# protoboard_rev01.net
KiCad netlist of a schematic drawn in EAGLE
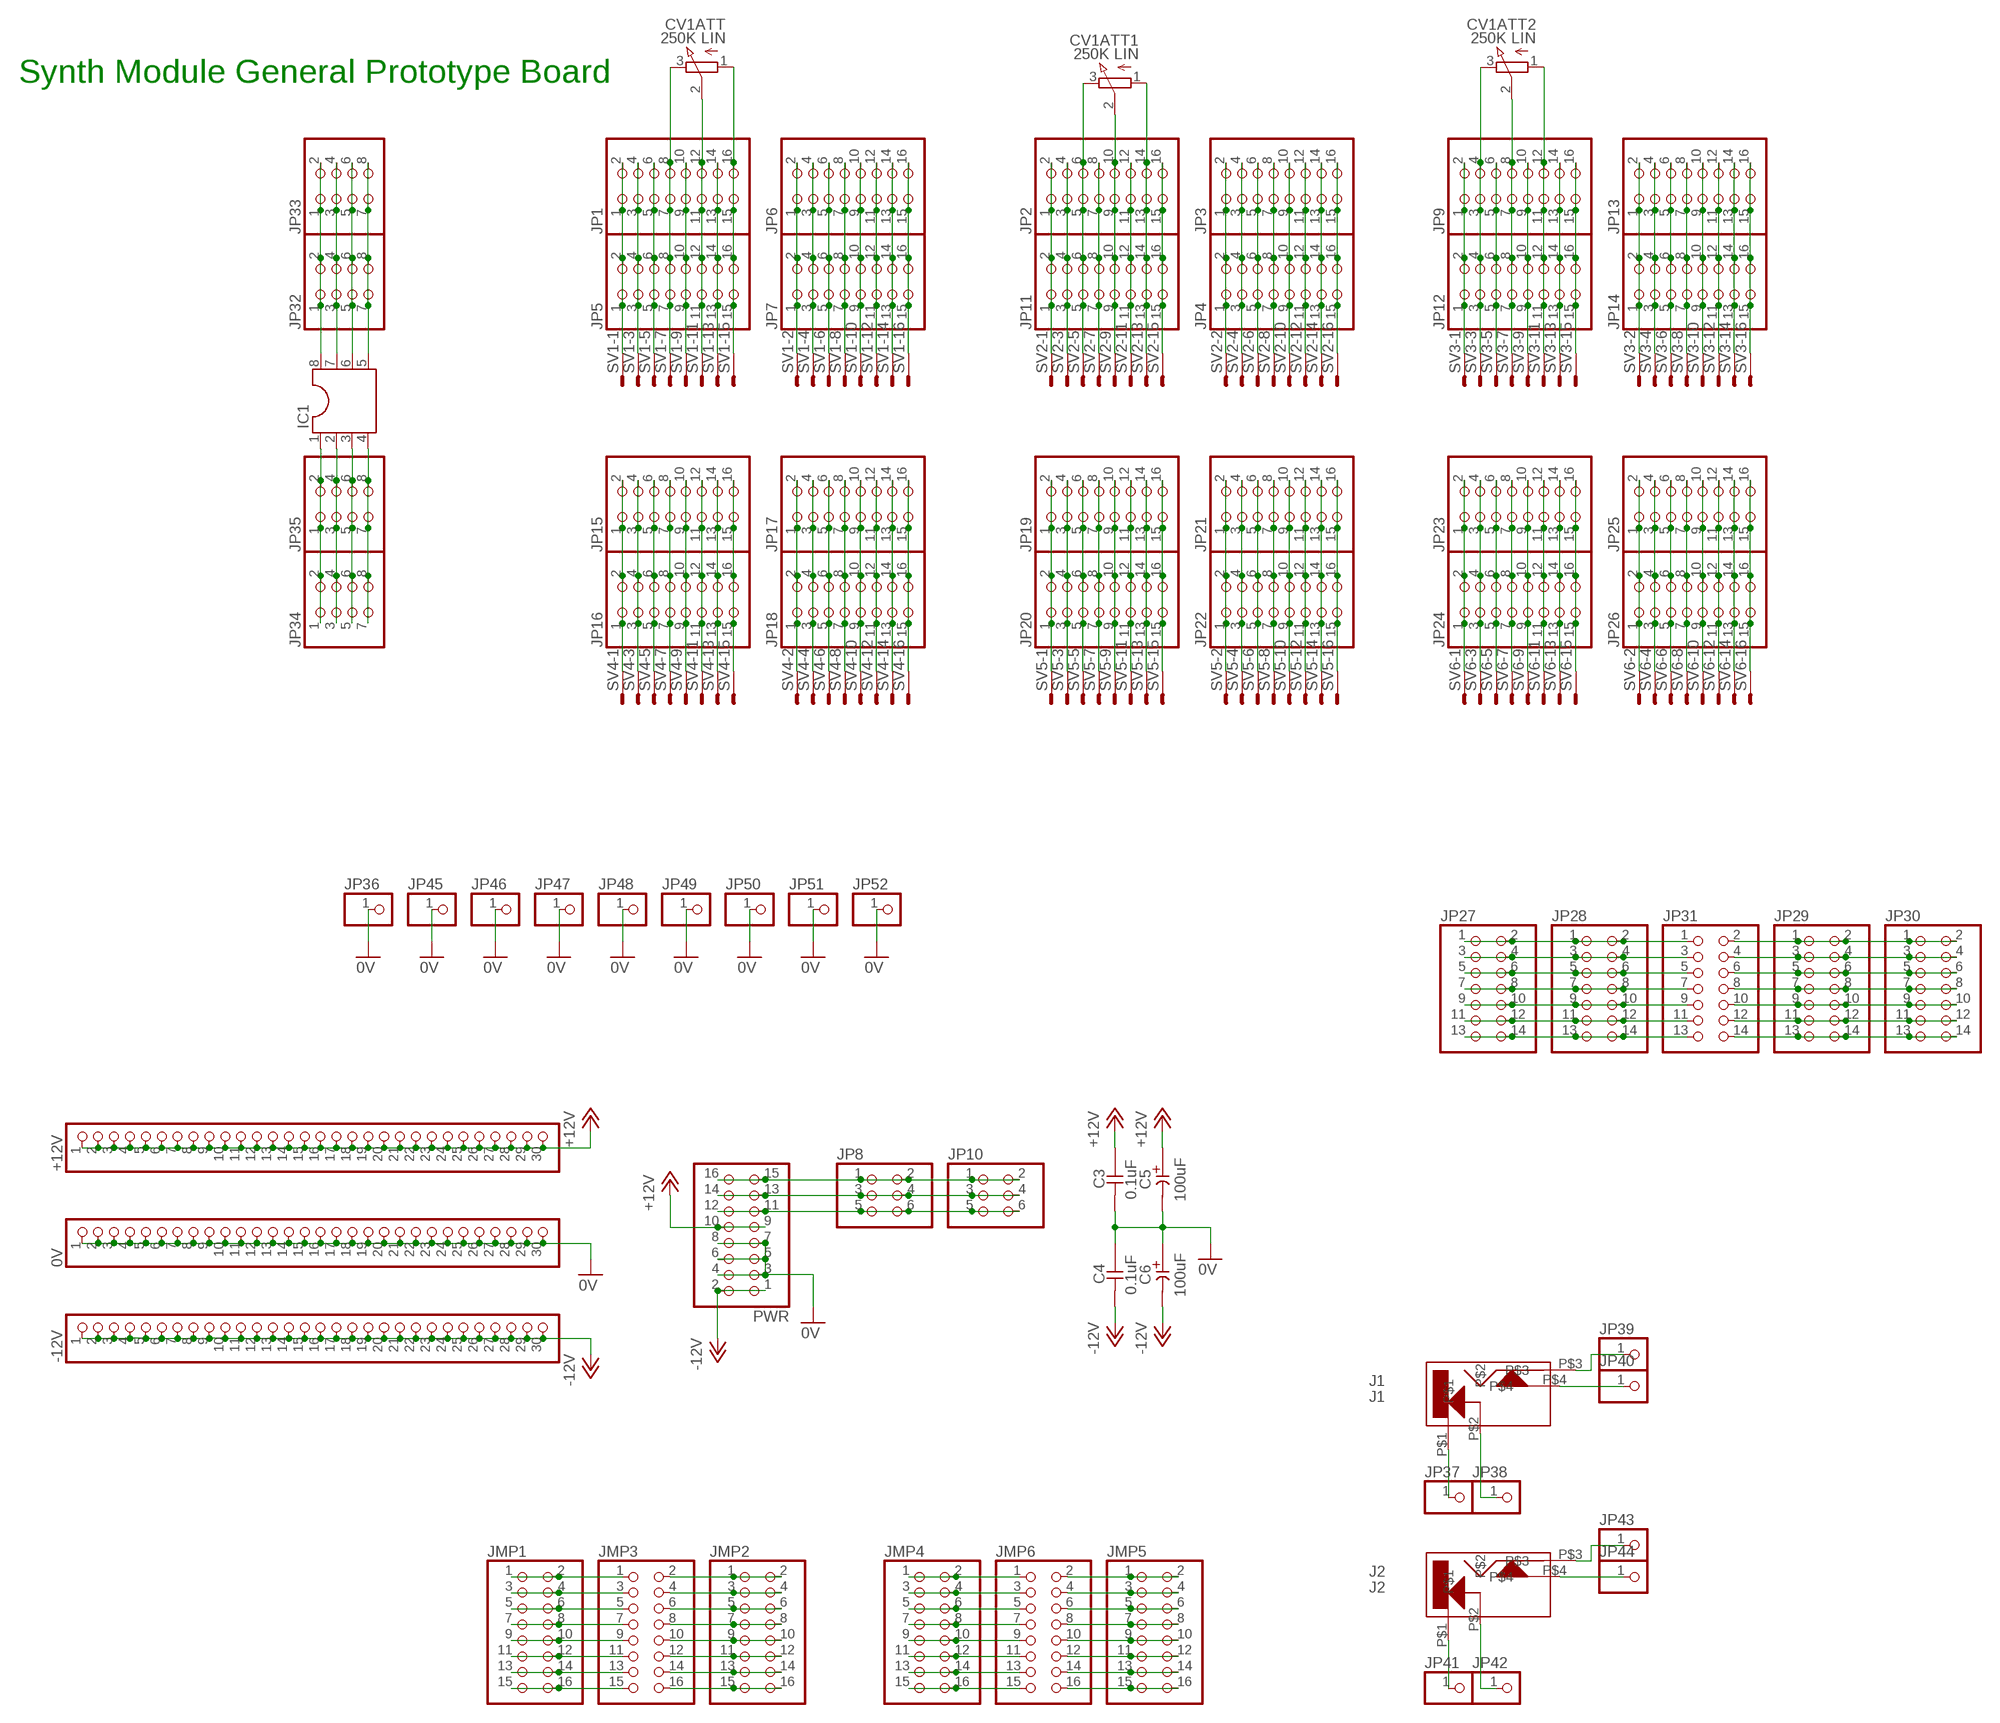
[diagram p0: schematic, sheet 1]

(export (version "E")
  (design (tool "Eeschema 10.0.6"))
  (components
    (comp (ref "+12V")
      (value "PINHD-1X30")
      (footprint "eagle-import:1X30")
      (libsource (lib "eagle-import") (part "PINHD-1X30"))
    )
    (comp (ref "-12V")
      (value "PINHD-1X30")
      (footprint "eagle-import:1X30")
      (libsource (lib "eagle-import") (part "PINHD-1X30"))
    )
    (comp (ref "0V")
      (value "PINHD-1X30")
      (footprint "eagle-import:1X30")
      (libsource (lib "eagle-import") (part "PINHD-1X30"))
    )
    (comp (ref "C3")
      (value "0.1uF")
      (footprint "eagle-import:C025-024X044")
      (libsource (lib "eagle-import") (part "CC-US025-024X044"))
    )
    (comp (ref "C4")
      (value "0.1uF")
      (footprint "eagle-import:C025-024X044")
      (libsource (lib "eagle-import") (part "CC-US025-024X044"))
    )
    (comp (ref "C5")
      (value "100uF")
      (footprint "eagle-import:E5-8,5")
      (libsource (lib "eagle-import") (part "CE-USE5-8.5"))
    )
    (comp (ref "C6")
      (value "100uF")
      (footprint "eagle-import:E5-8,5")
      (libsource (lib "eagle-import") (part "CE-USE5-8.5"))
    )
    (comp (ref "CV1ATT")
      (value "250K LIN")
      (footprint "eagle-import:3RP_1610N")
      (libsource (lib "eagle-import") (part "3RP/1610N"))
    )
    (comp (ref "CV1ATT1")
      (value "250K LIN")
      (footprint "eagle-import:3RP_1610N")
      (libsource (lib "eagle-import") (part "3RP/1610N"))
    )
    (comp (ref "CV1ATT2")
      (value "250K LIN")
      (footprint "eagle-import:3RP_1610N")
      (libsource (lib "eagle-import") (part "3RP/1610N"))
    )
    (comp (ref "IC1")
      (value "DIL8S")
      (footprint "eagle-import:SOCKET-08")
      (libsource (lib "eagle-import") (part "DIL8S"))
    )
    (comp (ref "J1")
      (value "J1")
      (footprint "eagle-import:CL1384")
      (libsource (lib "eagle-import") (part "CL1384"))
    )
    (comp (ref "J2")
      (value "J2")
      (footprint "eagle-import:CL1384")
      (libsource (lib "eagle-import") (part "CL1384"))
    )
    (comp (ref "JMP1")
      (value "PINHD-2X8")
      (footprint "eagle-import:2X08")
      (libsource (lib "eagle-import") (part "PINHD-2X8"))
    )
    (comp (ref "JMP2")
      (value "PINHD-2X8")
      (footprint "eagle-import:2X08")
      (libsource (lib "eagle-import") (part "PINHD-2X8"))
    )
    (comp (ref "JMP3")
      (value "PINHD-2X8")
      (footprint "eagle-import:2X08")
      (libsource (lib "eagle-import") (part "PINHD-2X8"))
    )
    (comp (ref "JMP4")
      (value "PINHD-2X8")
      (footprint "eagle-import:2X08")
      (libsource (lib "eagle-import") (part "PINHD-2X8"))
    )
    (comp (ref "JMP5")
      (value "PINHD-2X8")
      (footprint "eagle-import:2X08")
      (libsource (lib "eagle-import") (part "PINHD-2X8"))
    )
    (comp (ref "JMP6")
      (value "PINHD-2X8")
      (footprint "eagle-import:2X08")
      (libsource (lib "eagle-import") (part "PINHD-2X8"))
    )
    (comp (ref "JP1")
      (value "PINHD-2X8")
      (footprint "eagle-import:2X08")
      (libsource (lib "eagle-import") (part "PINHD-2X8"))
    )
    (comp (ref "JP2")
      (value "PINHD-2X8")
      (footprint "eagle-import:2X08")
      (libsource (lib "eagle-import") (part "PINHD-2X8"))
    )
    (comp (ref "JP3")
      (value "PINHD-2X8")
      (footprint "eagle-import:2X08")
      (libsource (lib "eagle-import") (part "PINHD-2X8"))
    )
    (comp (ref "JP4")
      (value "PINHD-2X8")
      (footprint "eagle-import:2X08")
      (libsource (lib "eagle-import") (part "PINHD-2X8"))
    )
    (comp (ref "JP5")
      (value "PINHD-2X8")
      (footprint "eagle-import:2X08")
      (libsource (lib "eagle-import") (part "PINHD-2X8"))
    )
    (comp (ref "JP6")
      (value "PINHD-2X8")
      (footprint "eagle-import:2X08")
      (libsource (lib "eagle-import") (part "PINHD-2X8"))
    )
    (comp (ref "JP7")
      (value "PINHD-2X8")
      (footprint "eagle-import:2X08")
      (libsource (lib "eagle-import") (part "PINHD-2X8"))
    )
    (comp (ref "JP8")
      (value "PINHD-2X3")
      (footprint "eagle-import:2X03")
      (libsource (lib "eagle-import") (part "PINHD-2X3"))
    )
    (comp (ref "JP9")
      (value "PINHD-2X8")
      (footprint "eagle-import:2X08")
      (libsource (lib "eagle-import") (part "PINHD-2X8"))
    )
    (comp (ref "JP10")
      (value "PINHD-2X3")
      (footprint "eagle-import:2X03")
      (libsource (lib "eagle-import") (part "PINHD-2X3"))
    )
    (comp (ref "JP11")
      (value "PINHD-2X8")
      (footprint "eagle-import:2X08")
      (libsource (lib "eagle-import") (part "PINHD-2X8"))
    )
    (comp (ref "JP12")
      (value "PINHD-2X8")
      (footprint "eagle-import:2X08")
      (libsource (lib "eagle-import") (part "PINHD-2X8"))
    )
    (comp (ref "JP13")
      (value "PINHD-2X8")
      (footprint "eagle-import:2X08")
      (libsource (lib "eagle-import") (part "PINHD-2X8"))
    )
    (comp (ref "JP14")
      (value "PINHD-2X8")
      (footprint "eagle-import:2X08")
      (libsource (lib "eagle-import") (part "PINHD-2X8"))
    )
    (comp (ref "JP15")
      (value "PINHD-2X8")
      (footprint "eagle-import:2X08")
      (libsource (lib "eagle-import") (part "PINHD-2X8"))
    )
    (comp (ref "JP16")
      (value "PINHD-2X8")
      (footprint "eagle-import:2X08")
      (libsource (lib "eagle-import") (part "PINHD-2X8"))
    )
    (comp (ref "JP17")
      (value "PINHD-2X8")
      (footprint "eagle-import:2X08")
      (libsource (lib "eagle-import") (part "PINHD-2X8"))
    )
    (comp (ref "JP18")
      (value "PINHD-2X8")
      (footprint "eagle-import:2X08")
      (libsource (lib "eagle-import") (part "PINHD-2X8"))
    )
    (comp (ref "JP19")
      (value "PINHD-2X8")
      (footprint "eagle-import:2X08")
      (libsource (lib "eagle-import") (part "PINHD-2X8"))
    )
    (comp (ref "JP20")
      (value "PINHD-2X8")
      (footprint "eagle-import:2X08")
      (libsource (lib "eagle-import") (part "PINHD-2X8"))
    )
    (comp (ref "JP21")
      (value "PINHD-2X8")
      (footprint "eagle-import:2X08")
      (libsource (lib "eagle-import") (part "PINHD-2X8"))
    )
    (comp (ref "JP22")
      (value "PINHD-2X8")
      (footprint "eagle-import:2X08")
      (libsource (lib "eagle-import") (part "PINHD-2X8"))
    )
    (comp (ref "JP23")
      (value "PINHD-2X8")
      (footprint "eagle-import:2X08")
      (libsource (lib "eagle-import") (part "PINHD-2X8"))
    )
    (comp (ref "JP24")
      (value "PINHD-2X8")
      (footprint "eagle-import:2X08")
      (libsource (lib "eagle-import") (part "PINHD-2X8"))
    )
    (comp (ref "JP25")
      (value "PINHD-2X8")
      (footprint "eagle-import:2X08")
      (libsource (lib "eagle-import") (part "PINHD-2X8"))
    )
    (comp (ref "JP26")
      (value "PINHD-2X8")
      (footprint "eagle-import:2X08")
      (libsource (lib "eagle-import") (part "PINHD-2X8"))
    )
    (comp (ref "JP27")
      (value "PINHD-2X7")
      (footprint "eagle-import:2X07")
      (libsource (lib "eagle-import") (part "PINHD-2X7"))
    )
    (comp (ref "JP28")
      (value "PINHD-2X7")
      (footprint "eagle-import:2X07")
      (libsource (lib "eagle-import") (part "PINHD-2X7"))
    )
    (comp (ref "JP29")
      (value "PINHD-2X7")
      (footprint "eagle-import:2X07")
      (libsource (lib "eagle-import") (part "PINHD-2X7"))
    )
    (comp (ref "JP30")
      (value "PINHD-2X7")
      (footprint "eagle-import:2X07")
      (libsource (lib "eagle-import") (part "PINHD-2X7"))
    )
    (comp (ref "JP31")
      (value "PINHD-2X7")
      (footprint "eagle-import:2X07")
      (libsource (lib "eagle-import") (part "PINHD-2X7"))
    )
    (comp (ref "JP32")
      (value "PINHD-2X4")
      (footprint "eagle-import:2X04")
      (libsource (lib "eagle-import") (part "PINHD-2X4"))
    )
    (comp (ref "JP33")
      (value "PINHD-2X4")
      (footprint "eagle-import:2X04")
      (libsource (lib "eagle-import") (part "PINHD-2X4"))
    )
    (comp (ref "JP34")
      (value "PINHD-2X4")
      (footprint "eagle-import:2X04")
      (libsource (lib "eagle-import") (part "PINHD-2X4"))
    )
    (comp (ref "JP35")
      (value "PINHD-2X4")
      (footprint "eagle-import:2X04")
      (libsource (lib "eagle-import") (part "PINHD-2X4"))
    )
    (comp (ref "JP36")
      (value "PINHD-1X1")
      (footprint "eagle-import:1X01")
      (libsource (lib "eagle-import") (part "PINHD-1X1"))
    )
    (comp (ref "JP37")
      (value "PINHD-1X1")
      (footprint "eagle-import:1X01")
      (libsource (lib "eagle-import") (part "PINHD-1X1"))
    )
    (comp (ref "JP38")
      (value "PINHD-1X1")
      (footprint "eagle-import:1X01")
      (libsource (lib "eagle-import") (part "PINHD-1X1"))
    )
    (comp (ref "JP39")
      (value "PINHD-1X1")
      (footprint "eagle-import:1X01")
      (libsource (lib "eagle-import") (part "PINHD-1X1"))
    )
    (comp (ref "JP40")
      (value "PINHD-1X1")
      (footprint "eagle-import:1X01")
      (libsource (lib "eagle-import") (part "PINHD-1X1"))
    )
    (comp (ref "JP41")
      (value "PINHD-1X1")
      (footprint "eagle-import:1X01")
      (libsource (lib "eagle-import") (part "PINHD-1X1"))
    )
    (comp (ref "JP42")
      (value "PINHD-1X1")
      (footprint "eagle-import:1X01")
      (libsource (lib "eagle-import") (part "PINHD-1X1"))
    )
    (comp (ref "JP43")
      (value "PINHD-1X1")
      (footprint "eagle-import:1X01")
      (libsource (lib "eagle-import") (part "PINHD-1X1"))
    )
    (comp (ref "JP44")
      (value "PINHD-1X1")
      (footprint "eagle-import:1X01")
      (libsource (lib "eagle-import") (part "PINHD-1X1"))
    )
    (comp (ref "JP45")
      (value "PINHD-1X1")
      (footprint "eagle-import:1X01")
      (libsource (lib "eagle-import") (part "PINHD-1X1"))
    )
    (comp (ref "JP46")
      (value "PINHD-1X1")
      (footprint "eagle-import:1X01")
      (libsource (lib "eagle-import") (part "PINHD-1X1"))
    )
    (comp (ref "JP47")
      (value "PINHD-1X1")
      (footprint "eagle-import:1X01")
      (libsource (lib "eagle-import") (part "PINHD-1X1"))
    )
    (comp (ref "JP48")
      (value "PINHD-1X1")
      (footprint "eagle-import:1X01")
      (libsource (lib "eagle-import") (part "PINHD-1X1"))
    )
    (comp (ref "JP49")
      (value "PINHD-1X1")
      (footprint "eagle-import:1X01")
      (libsource (lib "eagle-import") (part "PINHD-1X1"))
    )
    (comp (ref "JP50")
      (value "PINHD-1X1")
      (footprint "eagle-import:1X01")
      (libsource (lib "eagle-import") (part "PINHD-1X1"))
    )
    (comp (ref "JP51")
      (value "PINHD-1X1")
      (footprint "eagle-import:1X01")
      (libsource (lib "eagle-import") (part "PINHD-1X1"))
    )
    (comp (ref "JP52")
      (value "PINHD-1X1")
      (footprint "eagle-import:1X01")
      (libsource (lib "eagle-import") (part "PINHD-1X1"))
    )
    (comp (ref "PWR")
      (value "PINHD-2X8")
      (footprint "eagle-import:2X08")
      (libsource (lib "eagle-import") (part "PINHD-2X8"))
    )
    (comp (ref "SV1")
      (value "16E")
      (footprint "eagle-import:16P")
      (libsource (lib "eagle-import") (part "16E"))
    )
    (comp (ref "SV2")
      (value "16E")
      (footprint "eagle-import:16P")
      (libsource (lib "eagle-import") (part "16E"))
    )
    (comp (ref "SV3")
      (value "16E")
      (footprint "eagle-import:16P")
      (libsource (lib "eagle-import") (part "16E"))
    )
    (comp (ref "SV4")
      (value "16E")
      (footprint "eagle-import:16P")
      (libsource (lib "eagle-import") (part "16E"))
    )
    (comp (ref "SV5")
      (value "16E")
      (footprint "eagle-import:16P")
      (libsource (lib "eagle-import") (part "16E"))
    )
    (comp (ref "SV6")
      (value "16E")
      (footprint "eagle-import:16P")
      (libsource (lib "eagle-import") (part "16E"))
    )
  )
  (nets
    (net (code "1") (name "+12V") (class "Default")
      (node (ref "+12V") (pin "1") (pinfunction "1_1") (pintype "passive"))
      (node (ref "+12V") (pin "10") (pinfunction "10_10") (pintype "passive"))
      (node (ref "+12V") (pin "11") (pinfunction "11_11") (pintype "passive"))
      (node (ref "+12V") (pin "12") (pinfunction "12_12") (pintype "passive"))
      (node (ref "+12V") (pin "13") (pinfunction "13_13") (pintype "passive"))
      (node (ref "+12V") (pin "14") (pinfunction "14_14") (pintype "passive"))
      (node (ref "+12V") (pin "15") (pinfunction "15_15") (pintype "passive"))
      (node (ref "+12V") (pin "16") (pinfunction "16_16") (pintype "passive"))
      (node (ref "+12V") (pin "17") (pinfunction "17_17") (pintype "passive"))
      (node (ref "+12V") (pin "18") (pinfunction "18_18") (pintype "passive"))
      (node (ref "+12V") (pin "19") (pinfunction "19_19") (pintype "passive"))
      (node (ref "+12V") (pin "2") (pinfunction "2_2") (pintype "passive"))
      (node (ref "+12V") (pin "20") (pinfunction "20_20") (pintype "passive"))
      (node (ref "+12V") (pin "21") (pinfunction "21_21") (pintype "passive"))
      (node (ref "+12V") (pin "22") (pinfunction "22_22") (pintype "passive"))
      (node (ref "+12V") (pin "23") (pinfunction "23_23") (pintype "passive"))
      (node (ref "+12V") (pin "24") (pinfunction "24_24") (pintype "passive"))
      (node (ref "+12V") (pin "25") (pinfunction "25_25") (pintype "passive"))
      (node (ref "+12V") (pin "26") (pinfunction "26_26") (pintype "passive"))
      (node (ref "+12V") (pin "27") (pinfunction "27_27") (pintype "passive"))
      (node (ref "+12V") (pin "28") (pinfunction "28_28") (pintype "passive"))
      (node (ref "+12V") (pin "29") (pinfunction "29_29") (pintype "passive"))
      (node (ref "+12V") (pin "3") (pinfunction "3_3") (pintype "passive"))
      (node (ref "+12V") (pin "30") (pinfunction "30_30") (pintype "passive"))
      (node (ref "+12V") (pin "4") (pinfunction "4_4") (pintype "passive"))
      (node (ref "+12V") (pin "5") (pinfunction "5_5") (pintype "passive"))
      (node (ref "+12V") (pin "6") (pinfunction "6_6") (pintype "passive"))
      (node (ref "+12V") (pin "7") (pinfunction "7_7") (pintype "passive"))
      (node (ref "+12V") (pin "8") (pinfunction "8_8") (pintype "passive"))
      (node (ref "+12V") (pin "9") (pinfunction "9_9") (pintype "passive"))
      (node (ref "C3") (pin "1") (pinfunction "1_1") (pintype "passive"))
      (node (ref "C5") (pin "+") (pinfunction "+_+") (pintype "passive"))
      (node (ref "PWR") (pin "10") (pinfunction "10_10") (pintype "passive"))
      (node (ref "PWR") (pin "9") (pinfunction "9_9") (pintype "passive"))
    )
    (net (code "2") (name "-12V") (class "Default")
      (node (ref "-12V") (pin "1") (pinfunction "1_1") (pintype "passive"))
      (node (ref "-12V") (pin "10") (pinfunction "10_10") (pintype "passive"))
      (node (ref "-12V") (pin "11") (pinfunction "11_11") (pintype "passive"))
      (node (ref "-12V") (pin "12") (pinfunction "12_12") (pintype "passive"))
      (node (ref "-12V") (pin "13") (pinfunction "13_13") (pintype "passive"))
      (node (ref "-12V") (pin "14") (pinfunction "14_14") (pintype "passive"))
      (node (ref "-12V") (pin "15") (pinfunction "15_15") (pintype "passive"))
      (node (ref "-12V") (pin "16") (pinfunction "16_16") (pintype "passive"))
      (node (ref "-12V") (pin "17") (pinfunction "17_17") (pintype "passive"))
      (node (ref "-12V") (pin "18") (pinfunction "18_18") (pintype "passive"))
      (node (ref "-12V") (pin "19") (pinfunction "19_19") (pintype "passive"))
      (node (ref "-12V") (pin "2") (pinfunction "2_2") (pintype "passive"))
      (node (ref "-12V") (pin "20") (pinfunction "20_20") (pintype "passive"))
      (node (ref "-12V") (pin "21") (pinfunction "21_21") (pintype "passive"))
      (node (ref "-12V") (pin "22") (pinfunction "22_22") (pintype "passive"))
      (node (ref "-12V") (pin "23") (pinfunction "23_23") (pintype "passive"))
      (node (ref "-12V") (pin "24") (pinfunction "24_24") (pintype "passive"))
      (node (ref "-12V") (pin "25") (pinfunction "25_25") (pintype "passive"))
      (node (ref "-12V") (pin "26") (pinfunction "26_26") (pintype "passive"))
      (node (ref "-12V") (pin "27") (pinfunction "27_27") (pintype "passive"))
      (node (ref "-12V") (pin "28") (pinfunction "28_28") (pintype "passive"))
      (node (ref "-12V") (pin "29") (pinfunction "29_29") (pintype "passive"))
      (node (ref "-12V") (pin "3") (pinfunction "3_3") (pintype "passive"))
      (node (ref "-12V") (pin "30") (pinfunction "30_30") (pintype "passive"))
      (node (ref "-12V") (pin "4") (pinfunction "4_4") (pintype "passive"))
      (node (ref "-12V") (pin "5") (pinfunction "5_5") (pintype "passive"))
      (node (ref "-12V") (pin "6") (pinfunction "6_6") (pintype "passive"))
      (node (ref "-12V") (pin "7") (pinfunction "7_7") (pintype "passive"))
      (node (ref "-12V") (pin "8") (pinfunction "8_8") (pintype "passive"))
      (node (ref "-12V") (pin "9") (pinfunction "9_9") (pintype "passive"))
      (node (ref "C4") (pin "2") (pinfunction "2_2") (pintype "passive"))
      (node (ref "C6") (pin "-") (pinfunction "-_-") (pintype "passive"))
      (node (ref "PWR") (pin "1") (pinfunction "1_1") (pintype "passive"))
      (node (ref "PWR") (pin "2") (pinfunction "2_2") (pintype "passive"))
    )
    (net (code "3") (name "0V") (class "Default")
      (node (ref "0V") (pin "1") (pinfunction "1_1") (pintype "passive"))
      (node (ref "0V") (pin "10") (pinfunction "10_10") (pintype "passive"))
      (node (ref "0V") (pin "11") (pinfunction "11_11") (pintype "passive"))
      (node (ref "0V") (pin "12") (pinfunction "12_12") (pintype "passive"))
      (node (ref "0V") (pin "13") (pinfunction "13_13") (pintype "passive"))
      (node (ref "0V") (pin "14") (pinfunction "14_14") (pintype "passive"))
      (node (ref "0V") (pin "15") (pinfunction "15_15") (pintype "passive"))
      (node (ref "0V") (pin "16") (pinfunction "16_16") (pintype "passive"))
      (node (ref "0V") (pin "17") (pinfunction "17_17") (pintype "passive"))
      (node (ref "0V") (pin "18") (pinfunction "18_18") (pintype "passive"))
      (node (ref "0V") (pin "19") (pinfunction "19_19") (pintype "passive"))
      (node (ref "0V") (pin "2") (pinfunction "2_2") (pintype "passive"))
      (node (ref "0V") (pin "20") (pinfunction "20_20") (pintype "passive"))
      (node (ref "0V") (pin "21") (pinfunction "21_21") (pintype "passive"))
      (node (ref "0V") (pin "22") (pinfunction "22_22") (pintype "passive"))
      (node (ref "0V") (pin "23") (pinfunction "23_23") (pintype "passive"))
      (node (ref "0V") (pin "24") (pinfunction "24_24") (pintype "passive"))
      (node (ref "0V") (pin "25") (pinfunction "25_25") (pintype "passive"))
      (node (ref "0V") (pin "26") (pinfunction "26_26") (pintype "passive"))
      (node (ref "0V") (pin "27") (pinfunction "27_27") (pintype "passive"))
      (node (ref "0V") (pin "28") (pinfunction "28_28") (pintype "passive"))
      (node (ref "0V") (pin "29") (pinfunction "29_29") (pintype "passive"))
      (node (ref "0V") (pin "3") (pinfunction "3_3") (pintype "passive"))
      (node (ref "0V") (pin "30") (pinfunction "30_30") (pintype "passive"))
      (node (ref "0V") (pin "4") (pinfunction "4_4") (pintype "passive"))
      (node (ref "0V") (pin "5") (pinfunction "5_5") (pintype "passive"))
      (node (ref "0V") (pin "6") (pinfunction "6_6") (pintype "passive"))
      (node (ref "0V") (pin "7") (pinfunction "7_7") (pintype "passive"))
      (node (ref "0V") (pin "8") (pinfunction "8_8") (pintype "passive"))
      (node (ref "0V") (pin "9") (pinfunction "9_9") (pintype "passive"))
      (node (ref "C3") (pin "2") (pinfunction "2_2") (pintype "passive"))
      (node (ref "C4") (pin "1") (pinfunction "1_1") (pintype "passive"))
      (node (ref "C5") (pin "-") (pinfunction "-_-") (pintype "passive"))
      (node (ref "C6") (pin "+") (pinfunction "+_+") (pintype "passive"))
      (node (ref "JP36") (pin "1") (pinfunction "1_1") (pintype "passive"))
      (node (ref "JP45") (pin "1") (pinfunction "1_1") (pintype "passive"))
      (node (ref "JP46") (pin "1") (pinfunction "1_1") (pintype "passive"))
      (node (ref "JP47") (pin "1") (pinfunction "1_1") (pintype "passive"))
      (node (ref "JP48") (pin "1") (pinfunction "1_1") (pintype "passive"))
      (node (ref "JP49") (pin "1") (pinfunction "1_1") (pintype "passive"))
      (node (ref "JP50") (pin "1") (pinfunction "1_1") (pintype "passive"))
      (node (ref "JP51") (pin "1") (pinfunction "1_1") (pintype "passive"))
      (node (ref "JP52") (pin "1") (pinfunction "1_1") (pintype "passive"))
      (node (ref "PWR") (pin "3") (pinfunction "3_3") (pintype "passive"))
      (node (ref "PWR") (pin "4") (pinfunction "4_4") (pintype "passive"))
      (node (ref "PWR") (pin "5") (pinfunction "5_5") (pintype "passive"))
      (node (ref "PWR") (pin "6") (pinfunction "6_6") (pintype "passive"))
      (node (ref "PWR") (pin "7") (pinfunction "7_7") (pintype "passive"))
      (node (ref "PWR") (pin "8") (pinfunction "8_8") (pintype "passive"))
    )
    (net (code "4") (name "Net-(CV1ATT-A)") (class "Default")
      (node (ref "CV1ATT") (pin "1") (pinfunction "A_1") (pintype "passive"))
      (node (ref "JP1") (pin "15") (pinfunction "15_15") (pintype "passive"))
      (node (ref "JP1") (pin "16") (pinfunction "16_16") (pintype "passive"))
      (node (ref "JP5") (pin "15") (pinfunction "15_15") (pintype "passive"))
      (node (ref "JP5") (pin "16") (pinfunction "16_16") (pintype "passive"))
      (node (ref "SV1") (pin "15") (pinfunction "S_15") (pintype "passive"))
    )
    (net (code "5") (name "Net-(CV1ATT-E)") (class "Default")
      (node (ref "CV1ATT") (pin "3") (pinfunction "E_3") (pintype "passive"))
      (node (ref "JP1") (pin "7") (pinfunction "7_7") (pintype "passive"))
      (node (ref "JP1") (pin "8") (pinfunction "8_8") (pintype "passive"))
      (node (ref "JP5") (pin "7") (pinfunction "7_7") (pintype "passive"))
      (node (ref "JP5") (pin "8") (pinfunction "8_8") (pintype "passive"))
      (node (ref "SV1") (pin "7") (pinfunction "S_7") (pintype "passive"))
    )
    (net (code "6") (name "Net-(CV1ATT-S)") (class "Default")
      (node (ref "CV1ATT") (pin "2") (pinfunction "S_2") (pintype "passive"))
      (node (ref "JP1") (pin "11") (pinfunction "11_11") (pintype "passive"))
      (node (ref "JP1") (pin "12") (pinfunction "12_12") (pintype "passive"))
      (node (ref "JP5") (pin "11") (pinfunction "11_11") (pintype "passive"))
      (node (ref "JP5") (pin "12") (pinfunction "12_12") (pintype "passive"))
      (node (ref "SV1") (pin "11") (pinfunction "S_11") (pintype "passive"))
    )
    (net (code "7") (name "Net-(CV1ATT1-A)") (class "Default")
      (node (ref "CV1ATT1") (pin "1") (pinfunction "A_1") (pintype "passive"))
      (node (ref "JP11") (pin "13") (pinfunction "13_13") (pintype "passive"))
      (node (ref "JP11") (pin "14") (pinfunction "14_14") (pintype "passive"))
      (node (ref "JP2") (pin "13") (pinfunction "13_13") (pintype "passive"))
      (node (ref "JP2") (pin "14") (pinfunction "14_14") (pintype "passive"))
      (node (ref "SV2") (pin "13") (pinfunction "S_13") (pintype "passive"))
    )
    (net (code "8") (name "Net-(CV1ATT1-E)") (class "Default")
      (node (ref "CV1ATT1") (pin "3") (pinfunction "E_3") (pintype "passive"))
      (node (ref "JP11") (pin "5") (pinfunction "5_5") (pintype "passive"))
      (node (ref "JP11") (pin "6") (pinfunction "6_6") (pintype "passive"))
      (node (ref "JP2") (pin "5") (pinfunction "5_5") (pintype "passive"))
      (node (ref "JP2") (pin "6") (pinfunction "6_6") (pintype "passive"))
      (node (ref "SV2") (pin "5") (pinfunction "S_5") (pintype "passive"))
    )
    (net (code "9") (name "Net-(CV1ATT1-S)") (class "Default")
      (node (ref "CV1ATT1") (pin "2") (pinfunction "S_2") (pintype "passive"))
      (node (ref "JP11") (pin "10") (pinfunction "10_10") (pintype "passive"))
      (node (ref "JP11") (pin "9") (pinfunction "9_9") (pintype "passive"))
      (node (ref "JP2") (pin "10") (pinfunction "10_10") (pintype "passive"))
      (node (ref "JP2") (pin "9") (pinfunction "9_9") (pintype "passive"))
      (node (ref "SV2") (pin "9") (pinfunction "S_9") (pintype "passive"))
    )
    (net (code "10") (name "Net-(CV1ATT2-A)") (class "Default")
      (node (ref "CV1ATT2") (pin "1") (pinfunction "A_1") (pintype "passive"))
      (node (ref "JP12") (pin "11") (pinfunction "11_11") (pintype "passive"))
      (node (ref "JP12") (pin "12") (pinfunction "12_12") (pintype "passive"))
      (node (ref "JP9") (pin "11") (pinfunction "11_11") (pintype "passive"))
      (node (ref "JP9") (pin "12") (pinfunction "12_12") (pintype "passive"))
      (node (ref "SV3") (pin "11") (pinfunction "S_11") (pintype "passive"))
    )
    (net (code "11") (name "Net-(CV1ATT2-E)") (class "Default")
      (node (ref "CV1ATT2") (pin "3") (pinfunction "E_3") (pintype "passive"))
      (node (ref "JP12") (pin "3") (pinfunction "3_3") (pintype "passive"))
      (node (ref "JP12") (pin "4") (pinfunction "4_4") (pintype "passive"))
      (node (ref "JP9") (pin "3") (pinfunction "3_3") (pintype "passive"))
      (node (ref "JP9") (pin "4") (pinfunction "4_4") (pintype "passive"))
      (node (ref "SV3") (pin "3") (pinfunction "S_3") (pintype "passive"))
    )
    (net (code "12") (name "Net-(CV1ATT2-S)") (class "Default")
      (node (ref "CV1ATT2") (pin "2") (pinfunction "S_2") (pintype "passive"))
      (node (ref "JP12") (pin "7") (pinfunction "7_7") (pintype "passive"))
      (node (ref "JP12") (pin "8") (pinfunction "8_8") (pintype "passive"))
      (node (ref "JP9") (pin "7") (pinfunction "7_7") (pintype "passive"))
      (node (ref "JP9") (pin "8") (pinfunction "8_8") (pintype "passive"))
      (node (ref "SV3") (pin "7") (pinfunction "S_7") (pintype "passive"))
    )
    (net (code "13") (name "Net-(IC1-Pad1)") (class "Default")
      (node (ref "IC1") (pin "1") (pinfunction "1_1") (pintype "passive"))
      (node (ref "JP34") (pin "1") (pinfunction "1_1") (pintype "passive"))
      (node (ref "JP34") (pin "2") (pinfunction "2_2") (pintype "passive"))
      (node (ref "JP35") (pin "1") (pinfunction "1_1") (pintype "passive"))
      (node (ref "JP35") (pin "2") (pinfunction "2_2") (pintype "passive"))
    )
    (net (code "14") (name "Net-(IC1-Pad2)") (class "Default")
      (node (ref "IC1") (pin "2") (pinfunction "2_2") (pintype "passive"))
      (node (ref "JP34") (pin "3") (pinfunction "3_3") (pintype "passive"))
      (node (ref "JP34") (pin "4") (pinfunction "4_4") (pintype "passive"))
      (node (ref "JP35") (pin "3") (pinfunction "3_3") (pintype "passive"))
      (node (ref "JP35") (pin "4") (pinfunction "4_4") (pintype "passive"))
    )
    (net (code "15") (name "Net-(IC1-Pad3)") (class "Default")
      (node (ref "IC1") (pin "3") (pinfunction "3_3") (pintype "passive"))
      (node (ref "JP34") (pin "5") (pinfunction "5_5") (pintype "passive"))
      (node (ref "JP34") (pin "6") (pinfunction "6_6") (pintype "passive"))
      (node (ref "JP35") (pin "5") (pinfunction "5_5") (pintype "passive"))
      (node (ref "JP35") (pin "6") (pinfunction "6_6") (pintype "passive"))
    )
    (net (code "16") (name "Net-(IC1-Pad4)") (class "Default")
      (node (ref "IC1") (pin "4") (pinfunction "4_4") (pintype "passive"))
      (node (ref "JP34") (pin "7") (pinfunction "7_7") (pintype "passive"))
      (node (ref "JP34") (pin "8") (pinfunction "8_8") (pintype "passive"))
      (node (ref "JP35") (pin "7") (pinfunction "7_7") (pintype "passive"))
      (node (ref "JP35") (pin "8") (pinfunction "8_8") (pintype "passive"))
    )
    (net (code "17") (name "Net-(IC1-Pad5)") (class "Default")
      (node (ref "IC1") (pin "5") (pinfunction "5_5") (pintype "passive"))
      (node (ref "JP32") (pin "7") (pinfunction "7_7") (pintype "passive"))
      (node (ref "JP32") (pin "8") (pinfunction "8_8") (pintype "passive"))
      (node (ref "JP33") (pin "7") (pinfunction "7_7") (pintype "passive"))
      (node (ref "JP33") (pin "8") (pinfunction "8_8") (pintype "passive"))
    )
    (net (code "18") (name "Net-(IC1-Pad6)") (class "Default")
      (node (ref "IC1") (pin "6") (pinfunction "6_6") (pintype "passive"))
      (node (ref "JP32") (pin "5") (pinfunction "5_5") (pintype "passive"))
      (node (ref "JP32") (pin "6") (pinfunction "6_6") (pintype "passive"))
      (node (ref "JP33") (pin "5") (pinfunction "5_5") (pintype "passive"))
      (node (ref "JP33") (pin "6") (pinfunction "6_6") (pintype "passive"))
    )
    (net (code "19") (name "Net-(IC1-Pad7)") (class "Default")
      (node (ref "IC1") (pin "7") (pinfunction "7_7") (pintype "passive"))
      (node (ref "JP32") (pin "3") (pinfunction "3_3") (pintype "passive"))
      (node (ref "JP32") (pin "4") (pinfunction "4_4") (pintype "passive"))
      (node (ref "JP33") (pin "3") (pinfunction "3_3") (pintype "passive"))
      (node (ref "JP33") (pin "4") (pinfunction "4_4") (pintype "passive"))
    )
    (net (code "20") (name "Net-(IC1-Pad8)") (class "Default")
      (node (ref "IC1") (pin "8") (pinfunction "8_8") (pintype "passive"))
      (node (ref "JP32") (pin "1") (pinfunction "1_1") (pintype "passive"))
      (node (ref "JP32") (pin "2") (pinfunction "2_2") (pintype "passive"))
      (node (ref "JP33") (pin "1") (pinfunction "1_1") (pintype "passive"))
      (node (ref "JP33") (pin "2") (pinfunction "2_2") (pintype "passive"))
    )
    (net (code "21") (name "Net-(J1-PadP$1)") (class "Default")
      (node (ref "J1") (pin "P$1") (pinfunction "P$1_P$1") (pintype "bidirectional"))
      (node (ref "JP37") (pin "1") (pinfunction "1_1") (pintype "passive"))
    )
    (net (code "22") (name "Net-(J1-PadP$2)") (class "Default")
      (node (ref "J1") (pin "P$2") (pinfunction "P$2_P$2") (pintype "bidirectional"))
      (node (ref "JP38") (pin "1") (pinfunction "1_1") (pintype "passive"))
    )
    (net (code "23") (name "Net-(J1-PadP$3)") (class "Default")
      (node (ref "J1") (pin "P$3") (pinfunction "P$3_P$3") (pintype "bidirectional"))
      (node (ref "JP39") (pin "1") (pinfunction "1_1") (pintype "passive"))
    )
    (net (code "24") (name "Net-(J1-PadP$4)") (class "Default")
      (node (ref "J1") (pin "P$4") (pinfunction "P$4_P$4") (pintype "bidirectional"))
      (node (ref "JP40") (pin "1") (pinfunction "1_1") (pintype "passive"))
    )
    (net (code "25") (name "Net-(J2-PadP$1)") (class "Default")
      (node (ref "J2") (pin "P$1") (pinfunction "P$1_P$1") (pintype "bidirectional"))
      (node (ref "JP41") (pin "1") (pinfunction "1_1") (pintype "passive"))
    )
    (net (code "26") (name "Net-(J2-PadP$2)") (class "Default")
      (node (ref "J2") (pin "P$2") (pinfunction "P$2_P$2") (pintype "bidirectional"))
      (node (ref "JP42") (pin "1") (pinfunction "1_1") (pintype "passive"))
    )
    (net (code "27") (name "Net-(J2-PadP$3)") (class "Default")
      (node (ref "J2") (pin "P$3") (pinfunction "P$3_P$3") (pintype "bidirectional"))
      (node (ref "JP43") (pin "1") (pinfunction "1_1") (pintype "passive"))
    )
    (net (code "28") (name "Net-(J2-PadP$4)") (class "Default")
      (node (ref "J2") (pin "P$4") (pinfunction "P$4_P$4") (pintype "bidirectional"))
      (node (ref "JP44") (pin "1") (pinfunction "1_1") (pintype "passive"))
    )
    (net (code "29") (name "Net-(JMP1-Pad1)") (class "Default")
      (node (ref "JMP1") (pin "1") (pinfunction "1_1") (pintype "passive"))
      (node (ref "JMP1") (pin "2") (pinfunction "2_2") (pintype "passive"))
      (node (ref "JMP3") (pin "1") (pinfunction "1_1") (pintype "passive"))
    )
    (net (code "30") (name "Net-(JMP1-Pad3)") (class "Default")
      (node (ref "JMP1") (pin "3") (pinfunction "3_3") (pintype "passive"))
      (node (ref "JMP1") (pin "4") (pinfunction "4_4") (pintype "passive"))
      (node (ref "JMP3") (pin "3") (pinfunction "3_3") (pintype "passive"))
    )
    (net (code "31") (name "Net-(JMP1-Pad5)") (class "Default")
      (node (ref "JMP1") (pin "5") (pinfunction "5_5") (pintype "passive"))
      (node (ref "JMP1") (pin "6") (pinfunction "6_6") (pintype "passive"))
      (node (ref "JMP3") (pin "5") (pinfunction "5_5") (pintype "passive"))
    )
    (net (code "32") (name "Net-(JMP1-Pad7)") (class "Default")
      (node (ref "JMP1") (pin "7") (pinfunction "7_7") (pintype "passive"))
      (node (ref "JMP1") (pin "8") (pinfunction "8_8") (pintype "passive"))
      (node (ref "JMP3") (pin "7") (pinfunction "7_7") (pintype "passive"))
    )
    (net (code "33") (name "Net-(JMP1-Pad10)") (class "Default")
      (node (ref "JMP1") (pin "10") (pinfunction "10_10") (pintype "passive"))
      (node (ref "JMP1") (pin "9") (pinfunction "9_9") (pintype "passive"))
      (node (ref "JMP3") (pin "9") (pinfunction "9_9") (pintype "passive"))
    )
    (net (code "34") (name "Net-(JMP1-Pad11)") (class "Default")
      (node (ref "JMP1") (pin "11") (pinfunction "11_11") (pintype "passive"))
      (node (ref "JMP1") (pin "12") (pinfunction "12_12") (pintype "passive"))
      (node (ref "JMP3") (pin "11") (pinfunction "11_11") (pintype "passive"))
    )
    (net (code "35") (name "Net-(JMP1-Pad13)") (class "Default")
      (node (ref "JMP1") (pin "13") (pinfunction "13_13") (pintype "passive"))
      (node (ref "JMP1") (pin "14") (pinfunction "14_14") (pintype "passive"))
      (node (ref "JMP3") (pin "13") (pinfunction "13_13") (pintype "passive"))
    )
    (net (code "36") (name "Net-(JMP1-Pad15)") (class "Default")
      (node (ref "JMP1") (pin "15") (pinfunction "15_15") (pintype "passive"))
      (node (ref "JMP1") (pin "16") (pinfunction "16_16") (pintype "passive"))
      (node (ref "JMP3") (pin "15") (pinfunction "15_15") (pintype "passive"))
    )
    (net (code "37") (name "Net-(JMP2-Pad1)") (class "Default")
      (node (ref "JMP2") (pin "1") (pinfunction "1_1") (pintype "passive"))
      (node (ref "JMP2") (pin "2") (pinfunction "2_2") (pintype "passive"))
      (node (ref "JMP3") (pin "2") (pinfunction "2_2") (pintype "passive"))
    )
    (net (code "38") (name "Net-(JMP2-Pad3)") (class "Default")
      (node (ref "JMP2") (pin "3") (pinfunction "3_3") (pintype "passive"))
      (node (ref "JMP2") (pin "4") (pinfunction "4_4") (pintype "passive"))
      (node (ref "JMP3") (pin "4") (pinfunction "4_4") (pintype "passive"))
    )
    (net (code "39") (name "Net-(JMP2-Pad5)") (class "Default")
      (node (ref "JMP2") (pin "5") (pinfunction "5_5") (pintype "passive"))
      (node (ref "JMP2") (pin "6") (pinfunction "6_6") (pintype "passive"))
      (node (ref "JMP3") (pin "6") (pinfunction "6_6") (pintype "passive"))
    )
    (net (code "40") (name "Net-(JMP2-Pad7)") (class "Default")
      (node (ref "JMP2") (pin "7") (pinfunction "7_7") (pintype "passive"))
      (node (ref "JMP2") (pin "8") (pinfunction "8_8") (pintype "passive"))
      (node (ref "JMP3") (pin "8") (pinfunction "8_8") (pintype "passive"))
    )
    (net (code "41") (name "Net-(JMP2-Pad10)") (class "Default")
      (node (ref "JMP2") (pin "10") (pinfunction "10_10") (pintype "passive"))
      (node (ref "JMP2") (pin "9") (pinfunction "9_9") (pintype "passive"))
      (node (ref "JMP3") (pin "10") (pinfunction "10_10") (pintype "passive"))
    )
    (net (code "42") (name "Net-(JMP2-Pad11)") (class "Default")
      (node (ref "JMP2") (pin "11") (pinfunction "11_11") (pintype "passive"))
      (node (ref "JMP2") (pin "12") (pinfunction "12_12") (pintype "passive"))
      (node (ref "JMP3") (pin "12") (pinfunction "12_12") (pintype "passive"))
    )
    (net (code "43") (name "Net-(JMP2-Pad13)") (class "Default")
      (node (ref "JMP2") (pin "13") (pinfunction "13_13") (pintype "passive"))
      (node (ref "JMP2") (pin "14") (pinfunction "14_14") (pintype "passive"))
      (node (ref "JMP3") (pin "14") (pinfunction "14_14") (pintype "passive"))
    )
    (net (code "44") (name "Net-(JMP2-Pad15)") (class "Default")
      (node (ref "JMP2") (pin "15") (pinfunction "15_15") (pintype "passive"))
      (node (ref "JMP2") (pin "16") (pinfunction "16_16") (pintype "passive"))
      (node (ref "JMP3") (pin "16") (pinfunction "16_16") (pintype "passive"))
    )
    (net (code "45") (name "Net-(JMP4-Pad1)") (class "Default")
      (node (ref "JMP4") (pin "1") (pinfunction "1_1") (pintype "passive"))
      (node (ref "JMP4") (pin "2") (pinfunction "2_2") (pintype "passive"))
      (node (ref "JMP6") (pin "1") (pinfunction "1_1") (pintype "passive"))
    )
    (net (code "46") (name "Net-(JMP4-Pad3)") (class "Default")
      (node (ref "JMP4") (pin "3") (pinfunction "3_3") (pintype "passive"))
      (node (ref "JMP4") (pin "4") (pinfunction "4_4") (pintype "passive"))
      (node (ref "JMP6") (pin "3") (pinfunction "3_3") (pintype "passive"))
    )
    (net (code "47") (name "Net-(JMP4-Pad5)") (class "Default")
      (node (ref "JMP4") (pin "5") (pinfunction "5_5") (pintype "passive"))
      (node (ref "JMP4") (pin "6") (pinfunction "6_6") (pintype "passive"))
      (node (ref "JMP6") (pin "5") (pinfunction "5_5") (pintype "passive"))
    )
    (net (code "48") (name "Net-(JMP4-Pad7)") (class "Default")
      (node (ref "JMP4") (pin "7") (pinfunction "7_7") (pintype "passive"))
      (node (ref "JMP4") (pin "8") (pinfunction "8_8") (pintype "passive"))
      (node (ref "JMP6") (pin "7") (pinfunction "7_7") (pintype "passive"))
    )
    (net (code "49") (name "Net-(JMP4-Pad10)") (class "Default")
      (node (ref "JMP4") (pin "10") (pinfunction "10_10") (pintype "passive"))
      (node (ref "JMP4") (pin "9") (pinfunction "9_9") (pintype "passive"))
      (node (ref "JMP6") (pin "9") (pinfunction "9_9") (pintype "passive"))
    )
    (net (code "50") (name "Net-(JMP4-Pad11)") (class "Default")
      (node (ref "JMP4") (pin "11") (pinfunction "11_11") (pintype "passive"))
      (node (ref "JMP4") (pin "12") (pinfunction "12_12") (pintype "passive"))
      (node (ref "JMP6") (pin "11") (pinfunction "11_11") (pintype "passive"))
    )
    (net (code "51") (name "Net-(JMP4-Pad13)") (class "Default")
      (node (ref "JMP4") (pin "13") (pinfunction "13_13") (pintype "passive"))
      (node (ref "JMP4") (pin "14") (pinfunction "14_14") (pintype "passive"))
      (node (ref "JMP6") (pin "13") (pinfunction "13_13") (pintype "passive"))
    )
    (net (code "52") (name "Net-(JMP4-Pad15)") (class "Default")
      (node (ref "JMP4") (pin "15") (pinfunction "15_15") (pintype "passive"))
      (node (ref "JMP4") (pin "16") (pinfunction "16_16") (pintype "passive"))
      (node (ref "JMP6") (pin "15") (pinfunction "15_15") (pintype "passive"))
    )
    (net (code "53") (name "Net-(JMP5-Pad1)") (class "Default")
      (node (ref "JMP5") (pin "1") (pinfunction "1_1") (pintype "passive"))
      (node (ref "JMP5") (pin "2") (pinfunction "2_2") (pintype "passive"))
      (node (ref "JMP6") (pin "2") (pinfunction "2_2") (pintype "passive"))
    )
    (net (code "54") (name "Net-(JMP5-Pad3)") (class "Default")
      (node (ref "JMP5") (pin "3") (pinfunction "3_3") (pintype "passive"))
      (node (ref "JMP5") (pin "4") (pinfunction "4_4") (pintype "passive"))
      (node (ref "JMP6") (pin "4") (pinfunction "4_4") (pintype "passive"))
    )
    (net (code "55") (name "Net-(JMP5-Pad5)") (class "Default")
      (node (ref "JMP5") (pin "5") (pinfunction "5_5") (pintype "passive"))
      (node (ref "JMP5") (pin "6") (pinfunction "6_6") (pintype "passive"))
      (node (ref "JMP6") (pin "6") (pinfunction "6_6") (pintype "passive"))
    )
    (net (code "56") (name "Net-(JMP5-Pad7)") (class "Default")
      (node (ref "JMP5") (pin "7") (pinfunction "7_7") (pintype "passive"))
      (node (ref "JMP5") (pin "8") (pinfunction "8_8") (pintype "passive"))
      (node (ref "JMP6") (pin "8") (pinfunction "8_8") (pintype "passive"))
    )
    (net (code "57") (name "Net-(JMP5-Pad10)") (class "Default")
      (node (ref "JMP5") (pin "10") (pinfunction "10_10") (pintype "passive"))
      (node (ref "JMP5") (pin "9") (pinfunction "9_9") (pintype "passive"))
      (node (ref "JMP6") (pin "10") (pinfunction "10_10") (pintype "passive"))
    )
    (net (code "58") (name "Net-(JMP5-Pad11)") (class "Default")
      (node (ref "JMP5") (pin "11") (pinfunction "11_11") (pintype "passive"))
      (node (ref "JMP5") (pin "12") (pinfunction "12_12") (pintype "passive"))
      (node (ref "JMP6") (pin "12") (pinfunction "12_12") (pintype "passive"))
    )
    (net (code "59") (name "Net-(JMP5-Pad13)") (class "Default")
      (node (ref "JMP5") (pin "13") (pinfunction "13_13") (pintype "passive"))
      (node (ref "JMP5") (pin "14") (pinfunction "14_14") (pintype "passive"))
      (node (ref "JMP6") (pin "14") (pinfunction "14_14") (pintype "passive"))
    )
    (net (code "60") (name "Net-(JMP5-Pad15)") (class "Default")
      (node (ref "JMP5") (pin "15") (pinfunction "15_15") (pintype "passive"))
      (node (ref "JMP5") (pin "16") (pinfunction "16_16") (pintype "passive"))
      (node (ref "JMP6") (pin "16") (pinfunction "16_16") (pintype "passive"))
    )
    (net (code "61") (name "Net-(JP10-Pad1)") (class "Default")
      (node (ref "JP10") (pin "1") (pinfunction "1_1") (pintype "passive"))
      (node (ref "JP10") (pin "2") (pinfunction "2_2") (pintype "passive"))
      (node (ref "JP8") (pin "1") (pinfunction "1_1") (pintype "passive"))
      (node (ref "JP8") (pin "2") (pinfunction "2_2") (pintype "passive"))
      (node (ref "PWR") (pin "15") (pinfunction "15_15") (pintype "passive"))
      (node (ref "PWR") (pin "16") (pinfunction "16_16") (pintype "passive"))
    )
    (net (code "62") (name "Net-(JP10-Pad3)") (class "Default")
      (node (ref "JP10") (pin "3") (pinfunction "3_3") (pintype "passive"))
      (node (ref "JP10") (pin "4") (pinfunction "4_4") (pintype "passive"))
      (node (ref "JP8") (pin "3") (pinfunction "3_3") (pintype "passive"))
      (node (ref "JP8") (pin "4") (pinfunction "4_4") (pintype "passive"))
      (node (ref "PWR") (pin "13") (pinfunction "13_13") (pintype "passive"))
      (node (ref "PWR") (pin "14") (pinfunction "14_14") (pintype "passive"))
    )
    (net (code "63") (name "Net-(JP10-Pad5)") (class "Default")
      (node (ref "JP10") (pin "5") (pinfunction "5_5") (pintype "passive"))
      (node (ref "JP10") (pin "6") (pinfunction "6_6") (pintype "passive"))
      (node (ref "JP8") (pin "5") (pinfunction "5_5") (pintype "passive"))
      (node (ref "JP8") (pin "6") (pinfunction "6_6") (pintype "passive"))
      (node (ref "PWR") (pin "11") (pinfunction "11_11") (pintype "passive"))
      (node (ref "PWR") (pin "12") (pinfunction "12_12") (pintype "passive"))
    )
    (net (code "64") (name "Net-(JP27-Pad1)") (class "Default")
      (node (ref "JP27") (pin "1") (pinfunction "1_1") (pintype "passive"))
      (node (ref "JP27") (pin "2") (pinfunction "2_2") (pintype "passive"))
      (node (ref "JP28") (pin "1") (pinfunction "1_1") (pintype "passive"))
      (node (ref "JP28") (pin "2") (pinfunction "2_2") (pintype "passive"))
      (node (ref "JP31") (pin "1") (pinfunction "1_1") (pintype "passive"))
    )
    (net (code "65") (name "Net-(JP27-Pad3)") (class "Default")
      (node (ref "JP27") (pin "3") (pinfunction "3_3") (pintype "passive"))
      (node (ref "JP27") (pin "4") (pinfunction "4_4") (pintype "passive"))
      (node (ref "JP28") (pin "3") (pinfunction "3_3") (pintype "passive"))
      (node (ref "JP28") (pin "4") (pinfunction "4_4") (pintype "passive"))
      (node (ref "JP31") (pin "3") (pinfunction "3_3") (pintype "passive"))
    )
    (net (code "66") (name "Net-(JP27-Pad5)") (class "Default")
      (node (ref "JP27") (pin "5") (pinfunction "5_5") (pintype "passive"))
      (node (ref "JP27") (pin "6") (pinfunction "6_6") (pintype "passive"))
      (node (ref "JP28") (pin "5") (pinfunction "5_5") (pintype "passive"))
      (node (ref "JP28") (pin "6") (pinfunction "6_6") (pintype "passive"))
      (node (ref "JP31") (pin "5") (pinfunction "5_5") (pintype "passive"))
    )
    (net (code "67") (name "Net-(JP27-Pad7)") (class "Default")
      (node (ref "JP27") (pin "7") (pinfunction "7_7") (pintype "passive"))
      (node (ref "JP27") (pin "8") (pinfunction "8_8") (pintype "passive"))
      (node (ref "JP28") (pin "7") (pinfunction "7_7") (pintype "passive"))
      (node (ref "JP28") (pin "8") (pinfunction "8_8") (pintype "passive"))
      (node (ref "JP31") (pin "7") (pinfunction "7_7") (pintype "passive"))
    )
    (net (code "68") (name "Net-(JP27-Pad10)") (class "Default")
      (node (ref "JP27") (pin "10") (pinfunction "10_10") (pintype "passive"))
      (node (ref "JP27") (pin "9") (pinfunction "9_9") (pintype "passive"))
      (node (ref "JP28") (pin "10") (pinfunction "10_10") (pintype "passive"))
      (node (ref "JP28") (pin "9") (pinfunction "9_9") (pintype "passive"))
      (node (ref "JP31") (pin "9") (pinfunction "9_9") (pintype "passive"))
    )
    (net (code "69") (name "Net-(JP27-Pad11)") (class "Default")
      (node (ref "JP27") (pin "11") (pinfunction "11_11") (pintype "passive"))
      (node (ref "JP27") (pin "12") (pinfunction "12_12") (pintype "passive"))
      (node (ref "JP28") (pin "11") (pinfunction "11_11") (pintype "passive"))
      (node (ref "JP28") (pin "12") (pinfunction "12_12") (pintype "passive"))
      (node (ref "JP31") (pin "11") (pinfunction "11_11") (pintype "passive"))
    )
    (net (code "70") (name "Net-(JP27-Pad13)") (class "Default")
      (node (ref "JP27") (pin "13") (pinfunction "13_13") (pintype "passive"))
      (node (ref "JP27") (pin "14") (pinfunction "14_14") (pintype "passive"))
      (node (ref "JP28") (pin "13") (pinfunction "13_13") (pintype "passive"))
      (node (ref "JP28") (pin "14") (pinfunction "14_14") (pintype "passive"))
      (node (ref "JP31") (pin "13") (pinfunction "13_13") (pintype "passive"))
    )
    (net (code "71") (name "Net-(JP29-Pad1)") (class "Default")
      (node (ref "JP29") (pin "1") (pinfunction "1_1") (pintype "passive"))
      (node (ref "JP29") (pin "2") (pinfunction "2_2") (pintype "passive"))
      (node (ref "JP30") (pin "1") (pinfunction "1_1") (pintype "passive"))
      (node (ref "JP30") (pin "2") (pinfunction "2_2") (pintype "passive"))
      (node (ref "JP31") (pin "2") (pinfunction "2_2") (pintype "passive"))
    )
    (net (code "72") (name "Net-(JP29-Pad3)") (class "Default")
      (node (ref "JP29") (pin "3") (pinfunction "3_3") (pintype "passive"))
      (node (ref "JP29") (pin "4") (pinfunction "4_4") (pintype "passive"))
      (node (ref "JP30") (pin "3") (pinfunction "3_3") (pintype "passive"))
      (node (ref "JP30") (pin "4") (pinfunction "4_4") (pintype "passive"))
      (node (ref "JP31") (pin "4") (pinfunction "4_4") (pintype "passive"))
    )
    (net (code "73") (name "Net-(JP29-Pad5)") (class "Default")
      (node (ref "JP29") (pin "5") (pinfunction "5_5") (pintype "passive"))
      (node (ref "JP29") (pin "6") (pinfunction "6_6") (pintype "passive"))
      (node (ref "JP30") (pin "5") (pinfunction "5_5") (pintype "passive"))
      (node (ref "JP30") (pin "6") (pinfunction "6_6") (pintype "passive"))
      (node (ref "JP31") (pin "6") (pinfunction "6_6") (pintype "passive"))
    )
    (net (code "74") (name "Net-(JP29-Pad7)") (class "Default")
      (node (ref "JP29") (pin "7") (pinfunction "7_7") (pintype "passive"))
      (node (ref "JP29") (pin "8") (pinfunction "8_8") (pintype "passive"))
      (node (ref "JP30") (pin "7") (pinfunction "7_7") (pintype "passive"))
      (node (ref "JP30") (pin "8") (pinfunction "8_8") (pintype "passive"))
      (node (ref "JP31") (pin "8") (pinfunction "8_8") (pintype "passive"))
    )
    (net (code "75") (name "Net-(JP29-Pad10)") (class "Default")
      (node (ref "JP29") (pin "10") (pinfunction "10_10") (pintype "passive"))
      (node (ref "JP29") (pin "9") (pinfunction "9_9") (pintype "passive"))
      (node (ref "JP30") (pin "10") (pinfunction "10_10") (pintype "passive"))
      (node (ref "JP30") (pin "9") (pinfunction "9_9") (pintype "passive"))
      (node (ref "JP31") (pin "10") (pinfunction "10_10") (pintype "passive"))
    )
    (net (code "76") (name "Net-(JP29-Pad11)") (class "Default")
      (node (ref "JP29") (pin "11") (pinfunction "11_11") (pintype "passive"))
      (node (ref "JP29") (pin "12") (pinfunction "12_12") (pintype "passive"))
      (node (ref "JP30") (pin "11") (pinfunction "11_11") (pintype "passive"))
      (node (ref "JP30") (pin "12") (pinfunction "12_12") (pintype "passive"))
      (node (ref "JP31") (pin "12") (pinfunction "12_12") (pintype "passive"))
    )
    (net (code "77") (name "Net-(JP29-Pad13)") (class "Default")
      (node (ref "JP29") (pin "13") (pinfunction "13_13") (pintype "passive"))
      (node (ref "JP29") (pin "14") (pinfunction "14_14") (pintype "passive"))
      (node (ref "JP30") (pin "13") (pinfunction "13_13") (pintype "passive"))
      (node (ref "JP30") (pin "14") (pinfunction "14_14") (pintype "passive"))
      (node (ref "JP31") (pin "14") (pinfunction "14_14") (pintype "passive"))
    )
    (net (code "78") (name "Net-(SV1A-S)") (class "Default")
      (node (ref "JP1") (pin "1") (pinfunction "1_1") (pintype "passive"))
      (node (ref "JP1") (pin "2") (pinfunction "2_2") (pintype "passive"))
      (node (ref "JP5") (pin "1") (pinfunction "1_1") (pintype "passive"))
      (node (ref "JP5") (pin "2") (pinfunction "2_2") (pintype "passive"))
      (node (ref "SV1") (pin "1") (pinfunction "S_1") (pintype "passive"))
    )
    (net (code "79") (name "Net-(SV1B-S)") (class "Default")
      (node (ref "JP6") (pin "10") (pinfunction "10_10") (pintype "passive"))
      (node (ref "JP6") (pin "9") (pinfunction "9_9") (pintype "passive"))
      (node (ref "JP7") (pin "10") (pinfunction "10_10") (pintype "passive"))
      (node (ref "JP7") (pin "9") (pinfunction "9_9") (pintype "passive"))
      (node (ref "SV1") (pin "10") (pinfunction "S_10") (pintype "passive"))
    )
    (net (code "80") (name "Net-(SV1D-S)") (class "Default")
      (node (ref "JP6") (pin "11") (pinfunction "11_11") (pintype "passive"))
      (node (ref "JP6") (pin "12") (pinfunction "12_12") (pintype "passive"))
      (node (ref "JP7") (pin "11") (pinfunction "11_11") (pintype "passive"))
      (node (ref "JP7") (pin "12") (pinfunction "12_12") (pintype "passive"))
      (node (ref "SV1") (pin "12") (pinfunction "S_12") (pintype "passive"))
    )
    (net (code "81") (name "Net-(SV1E-S)") (class "Default")
      (node (ref "JP1") (pin "13") (pinfunction "13_13") (pintype "passive"))
      (node (ref "JP1") (pin "14") (pinfunction "14_14") (pintype "passive"))
      (node (ref "JP5") (pin "13") (pinfunction "13_13") (pintype "passive"))
      (node (ref "JP5") (pin "14") (pinfunction "14_14") (pintype "passive"))
      (node (ref "SV1") (pin "13") (pinfunction "S_13") (pintype "passive"))
    )
    (net (code "82") (name "Net-(SV1F-S)") (class "Default")
      (node (ref "JP6") (pin "13") (pinfunction "13_13") (pintype "passive"))
      (node (ref "JP6") (pin "14") (pinfunction "14_14") (pintype "passive"))
      (node (ref "JP7") (pin "13") (pinfunction "13_13") (pintype "passive"))
      (node (ref "JP7") (pin "14") (pinfunction "14_14") (pintype "passive"))
      (node (ref "SV1") (pin "14") (pinfunction "S_14") (pintype "passive"))
    )
    (net (code "83") (name "Net-(SV1H-S)") (class "Default")
      (node (ref "JP6") (pin "15") (pinfunction "15_15") (pintype "passive"))
      (node (ref "JP6") (pin "16") (pinfunction "16_16") (pintype "passive"))
      (node (ref "JP7") (pin "15") (pinfunction "15_15") (pintype "passive"))
      (node (ref "JP7") (pin "16") (pinfunction "16_16") (pintype "passive"))
      (node (ref "SV1") (pin "16") (pinfunction "S_16") (pintype "passive"))
    )
    (net (code "84") (name "Net-(SV1I-S)") (class "Default")
      (node (ref "JP6") (pin "1") (pinfunction "1_1") (pintype "passive"))
      (node (ref "JP6") (pin "2") (pinfunction "2_2") (pintype "passive"))
      (node (ref "JP7") (pin "1") (pinfunction "1_1") (pintype "passive"))
      (node (ref "JP7") (pin "2") (pinfunction "2_2") (pintype "passive"))
      (node (ref "SV1") (pin "2") (pinfunction "S_2") (pintype "passive"))
    )
    (net (code "85") (name "Net-(SV1J-S)") (class "Default")
      (node (ref "JP1") (pin "3") (pinfunction "3_3") (pintype "passive"))
      (node (ref "JP1") (pin "4") (pinfunction "4_4") (pintype "passive"))
      (node (ref "JP5") (pin "3") (pinfunction "3_3") (pintype "passive"))
      (node (ref "JP5") (pin "4") (pinfunction "4_4") (pintype "passive"))
      (node (ref "SV1") (pin "3") (pinfunction "S_3") (pintype "passive"))
    )
    (net (code "86") (name "Net-(SV1K-S)") (class "Default")
      (node (ref "JP6") (pin "3") (pinfunction "3_3") (pintype "passive"))
      (node (ref "JP6") (pin "4") (pinfunction "4_4") (pintype "passive"))
      (node (ref "JP7") (pin "3") (pinfunction "3_3") (pintype "passive"))
      (node (ref "JP7") (pin "4") (pinfunction "4_4") (pintype "passive"))
      (node (ref "SV1") (pin "4") (pinfunction "S_4") (pintype "passive"))
    )
    (net (code "87") (name "Net-(SV1L-S)") (class "Default")
      (node (ref "JP1") (pin "5") (pinfunction "5_5") (pintype "passive"))
      (node (ref "JP1") (pin "6") (pinfunction "6_6") (pintype "passive"))
      (node (ref "JP5") (pin "5") (pinfunction "5_5") (pintype "passive"))
      (node (ref "JP5") (pin "6") (pinfunction "6_6") (pintype "passive"))
      (node (ref "SV1") (pin "5") (pinfunction "S_5") (pintype "passive"))
    )
    (net (code "88") (name "Net-(SV1M-S)") (class "Default")
      (node (ref "JP6") (pin "5") (pinfunction "5_5") (pintype "passive"))
      (node (ref "JP6") (pin "6") (pinfunction "6_6") (pintype "passive"))
      (node (ref "JP7") (pin "5") (pinfunction "5_5") (pintype "passive"))
      (node (ref "JP7") (pin "6") (pinfunction "6_6") (pintype "passive"))
      (node (ref "SV1") (pin "6") (pinfunction "S_6") (pintype "passive"))
    )
    (net (code "89") (name "Net-(SV1O-S)") (class "Default")
      (node (ref "JP6") (pin "7") (pinfunction "7_7") (pintype "passive"))
      (node (ref "JP6") (pin "8") (pinfunction "8_8") (pintype "passive"))
      (node (ref "JP7") (pin "7") (pinfunction "7_7") (pintype "passive"))
      (node (ref "JP7") (pin "8") (pinfunction "8_8") (pintype "passive"))
      (node (ref "SV1") (pin "8") (pinfunction "S_8") (pintype "passive"))
    )
    (net (code "90") (name "Net-(SV1P-S)") (class "Default")
      (node (ref "JP1") (pin "10") (pinfunction "10_10") (pintype "passive"))
      (node (ref "JP1") (pin "9") (pinfunction "9_9") (pintype "passive"))
      (node (ref "JP5") (pin "10") (pinfunction "10_10") (pintype "passive"))
      (node (ref "JP5") (pin "9") (pinfunction "9_9") (pintype "passive"))
      (node (ref "SV1") (pin "9") (pinfunction "S_9") (pintype "passive"))
    )
    (net (code "91") (name "Net-(SV2A-S)") (class "Default")
      (node (ref "JP11") (pin "1") (pinfunction "1_1") (pintype "passive"))
      (node (ref "JP11") (pin "2") (pinfunction "2_2") (pintype "passive"))
      (node (ref "JP2") (pin "1") (pinfunction "1_1") (pintype "passive"))
      (node (ref "JP2") (pin "2") (pinfunction "2_2") (pintype "passive"))
      (node (ref "SV2") (pin "1") (pinfunction "S_1") (pintype "passive"))
    )
    (net (code "92") (name "Net-(SV2B-S)") (class "Default")
      (node (ref "JP3") (pin "10") (pinfunction "10_10") (pintype "passive"))
      (node (ref "JP3") (pin "9") (pinfunction "9_9") (pintype "passive"))
      (node (ref "JP4") (pin "10") (pinfunction "10_10") (pintype "passive"))
      (node (ref "JP4") (pin "9") (pinfunction "9_9") (pintype "passive"))
      (node (ref "SV2") (pin "10") (pinfunction "S_10") (pintype "passive"))
    )
    (net (code "93") (name "Net-(SV2C-S)") (class "Default")
      (node (ref "JP11") (pin "11") (pinfunction "11_11") (pintype "passive"))
      (node (ref "JP11") (pin "12") (pinfunction "12_12") (pintype "passive"))
      (node (ref "JP2") (pin "11") (pinfunction "11_11") (pintype "passive"))
      (node (ref "JP2") (pin "12") (pinfunction "12_12") (pintype "passive"))
      (node (ref "SV2") (pin "11") (pinfunction "S_11") (pintype "passive"))
    )
    (net (code "94") (name "Net-(SV2D-S)") (class "Default")
      (node (ref "JP3") (pin "11") (pinfunction "11_11") (pintype "passive"))
      (node (ref "JP3") (pin "12") (pinfunction "12_12") (pintype "passive"))
      (node (ref "JP4") (pin "11") (pinfunction "11_11") (pintype "passive"))
      (node (ref "JP4") (pin "12") (pinfunction "12_12") (pintype "passive"))
      (node (ref "SV2") (pin "12") (pinfunction "S_12") (pintype "passive"))
    )
    (net (code "95") (name "Net-(SV2F-S)") (class "Default")
      (node (ref "JP3") (pin "13") (pinfunction "13_13") (pintype "passive"))
      (node (ref "JP3") (pin "14") (pinfunction "14_14") (pintype "passive"))
      (node (ref "JP4") (pin "13") (pinfunction "13_13") (pintype "passive"))
      (node (ref "JP4") (pin "14") (pinfunction "14_14") (pintype "passive"))
      (node (ref "SV2") (pin "14") (pinfunction "S_14") (pintype "passive"))
    )
    (net (code "96") (name "Net-(SV2G-S)") (class "Default")
      (node (ref "JP11") (pin "15") (pinfunction "15_15") (pintype "passive"))
      (node (ref "JP11") (pin "16") (pinfunction "16_16") (pintype "passive"))
      (node (ref "JP2") (pin "15") (pinfunction "15_15") (pintype "passive"))
      (node (ref "JP2") (pin "16") (pinfunction "16_16") (pintype "passive"))
      (node (ref "SV2") (pin "15") (pinfunction "S_15") (pintype "passive"))
    )
    (net (code "97") (name "Net-(SV2H-S)") (class "Default")
      (node (ref "JP3") (pin "15") (pinfunction "15_15") (pintype "passive"))
      (node (ref "JP3") (pin "16") (pinfunction "16_16") (pintype "passive"))
      (node (ref "JP4") (pin "15") (pinfunction "15_15") (pintype "passive"))
      (node (ref "JP4") (pin "16") (pinfunction "16_16") (pintype "passive"))
      (node (ref "SV2") (pin "16") (pinfunction "S_16") (pintype "passive"))
    )
    (net (code "98") (name "Net-(SV2I-S)") (class "Default")
      (node (ref "JP3") (pin "1") (pinfunction "1_1") (pintype "passive"))
      (node (ref "JP3") (pin "2") (pinfunction "2_2") (pintype "passive"))
      (node (ref "JP4") (pin "1") (pinfunction "1_1") (pintype "passive"))
      (node (ref "JP4") (pin "2") (pinfunction "2_2") (pintype "passive"))
      (node (ref "SV2") (pin "2") (pinfunction "S_2") (pintype "passive"))
    )
    (net (code "99") (name "Net-(SV2J-S)") (class "Default")
      (node (ref "JP11") (pin "3") (pinfunction "3_3") (pintype "passive"))
      (node (ref "JP11") (pin "4") (pinfunction "4_4") (pintype "passive"))
      (node (ref "JP2") (pin "3") (pinfunction "3_3") (pintype "passive"))
      (node (ref "JP2") (pin "4") (pinfunction "4_4") (pintype "passive"))
      (node (ref "SV2") (pin "3") (pinfunction "S_3") (pintype "passive"))
    )
    (net (code "100") (name "Net-(SV2K-S)") (class "Default")
      (node (ref "JP3") (pin "3") (pinfunction "3_3") (pintype "passive"))
      (node (ref "JP3") (pin "4") (pinfunction "4_4") (pintype "passive"))
      (node (ref "JP4") (pin "3") (pinfunction "3_3") (pintype "passive"))
      (node (ref "JP4") (pin "4") (pinfunction "4_4") (pintype "passive"))
      (node (ref "SV2") (pin "4") (pinfunction "S_4") (pintype "passive"))
    )
    (net (code "101") (name "Net-(SV2M-S)") (class "Default")
      (node (ref "JP3") (pin "5") (pinfunction "5_5") (pintype "passive"))
      (node (ref "JP3") (pin "6") (pinfunction "6_6") (pintype "passive"))
      (node (ref "JP4") (pin "5") (pinfunction "5_5") (pintype "passive"))
      (node (ref "JP4") (pin "6") (pinfunction "6_6") (pintype "passive"))
      (node (ref "SV2") (pin "6") (pinfunction "S_6") (pintype "passive"))
    )
    (net (code "102") (name "Net-(SV2N-S)") (class "Default")
      (node (ref "JP11") (pin "7") (pinfunction "7_7") (pintype "passive"))
      (node (ref "JP11") (pin "8") (pinfunction "8_8") (pintype "passive"))
      (node (ref "JP2") (pin "7") (pinfunction "7_7") (pintype "passive"))
      (node (ref "JP2") (pin "8") (pinfunction "8_8") (pintype "passive"))
      (node (ref "SV2") (pin "7") (pinfunction "S_7") (pintype "passive"))
    )
    (net (code "103") (name "Net-(SV2O-S)") (class "Default")
      (node (ref "JP3") (pin "7") (pinfunction "7_7") (pintype "passive"))
      (node (ref "JP3") (pin "8") (pinfunction "8_8") (pintype "passive"))
      (node (ref "JP4") (pin "7") (pinfunction "7_7") (pintype "passive"))
      (node (ref "JP4") (pin "8") (pinfunction "8_8") (pintype "passive"))
      (node (ref "SV2") (pin "8") (pinfunction "S_8") (pintype "passive"))
    )
    (net (code "104") (name "Net-(SV3A-S)") (class "Default")
      (node (ref "JP12") (pin "1") (pinfunction "1_1") (pintype "passive"))
      (node (ref "JP12") (pin "2") (pinfunction "2_2") (pintype "passive"))
      (node (ref "JP9") (pin "1") (pinfunction "1_1") (pintype "passive"))
      (node (ref "JP9") (pin "2") (pinfunction "2_2") (pintype "passive"))
      (node (ref "SV3") (pin "1") (pinfunction "S_1") (pintype "passive"))
    )
    (net (code "105") (name "Net-(SV3B-S)") (class "Default")
      (node (ref "JP13") (pin "10") (pinfunction "10_10") (pintype "passive"))
      (node (ref "JP13") (pin "9") (pinfunction "9_9") (pintype "passive"))
      (node (ref "JP14") (pin "10") (pinfunction "10_10") (pintype "passive"))
      (node (ref "JP14") (pin "9") (pinfunction "9_9") (pintype "passive"))
      (node (ref "SV3") (pin "10") (pinfunction "S_10") (pintype "passive"))
    )
    (net (code "106") (name "Net-(SV3D-S)") (class "Default")
      (node (ref "JP13") (pin "11") (pinfunction "11_11") (pintype "passive"))
      (node (ref "JP13") (pin "12") (pinfunction "12_12") (pintype "passive"))
      (node (ref "JP14") (pin "11") (pinfunction "11_11") (pintype "passive"))
      (node (ref "JP14") (pin "12") (pinfunction "12_12") (pintype "passive"))
      (node (ref "SV3") (pin "12") (pinfunction "S_12") (pintype "passive"))
    )
    (net (code "107") (name "Net-(SV3E-S)") (class "Default")
      (node (ref "JP12") (pin "13") (pinfunction "13_13") (pintype "passive"))
      (node (ref "JP12") (pin "14") (pinfunction "14_14") (pintype "passive"))
      (node (ref "JP9") (pin "13") (pinfunction "13_13") (pintype "passive"))
      (node (ref "JP9") (pin "14") (pinfunction "14_14") (pintype "passive"))
      (node (ref "SV3") (pin "13") (pinfunction "S_13") (pintype "passive"))
    )
    (net (code "108") (name "Net-(SV3F-S)") (class "Default")
      (node (ref "JP13") (pin "13") (pinfunction "13_13") (pintype "passive"))
      (node (ref "JP13") (pin "14") (pinfunction "14_14") (pintype "passive"))
      (node (ref "JP14") (pin "13") (pinfunction "13_13") (pintype "passive"))
      (node (ref "JP14") (pin "14") (pinfunction "14_14") (pintype "passive"))
      (node (ref "SV3") (pin "14") (pinfunction "S_14") (pintype "passive"))
    )
    (net (code "109") (name "Net-(SV3G-S)") (class "Default")
      (node (ref "JP12") (pin "15") (pinfunction "15_15") (pintype "passive"))
      (node (ref "JP12") (pin "16") (pinfunction "16_16") (pintype "passive"))
      (node (ref "JP9") (pin "15") (pinfunction "15_15") (pintype "passive"))
      (node (ref "JP9") (pin "16") (pinfunction "16_16") (pintype "passive"))
      (node (ref "SV3") (pin "15") (pinfunction "S_15") (pintype "passive"))
    )
    (net (code "110") (name "Net-(SV3H-S)") (class "Default")
      (node (ref "JP13") (pin "15") (pinfunction "15_15") (pintype "passive"))
      (node (ref "JP13") (pin "16") (pinfunction "16_16") (pintype "passive"))
      (node (ref "JP14") (pin "15") (pinfunction "15_15") (pintype "passive"))
      (node (ref "JP14") (pin "16") (pinfunction "16_16") (pintype "passive"))
      (node (ref "SV3") (pin "16") (pinfunction "S_16") (pintype "passive"))
    )
    (net (code "111") (name "Net-(SV3I-S)") (class "Default")
      (node (ref "JP13") (pin "1") (pinfunction "1_1") (pintype "passive"))
      (node (ref "JP13") (pin "2") (pinfunction "2_2") (pintype "passive"))
      (node (ref "JP14") (pin "1") (pinfunction "1_1") (pintype "passive"))
      (node (ref "JP14") (pin "2") (pinfunction "2_2") (pintype "passive"))
      (node (ref "SV3") (pin "2") (pinfunction "S_2") (pintype "passive"))
    )
    (net (code "112") (name "Net-(SV3K-S)") (class "Default")
      (node (ref "JP13") (pin "3") (pinfunction "3_3") (pintype "passive"))
      (node (ref "JP13") (pin "4") (pinfunction "4_4") (pintype "passive"))
      (node (ref "JP14") (pin "3") (pinfunction "3_3") (pintype "passive"))
      (node (ref "JP14") (pin "4") (pinfunction "4_4") (pintype "passive"))
      (node (ref "SV3") (pin "4") (pinfunction "S_4") (pintype "passive"))
    )
    (net (code "113") (name "Net-(SV3L-S)") (class "Default")
      (node (ref "JP12") (pin "5") (pinfunction "5_5") (pintype "passive"))
      (node (ref "JP12") (pin "6") (pinfunction "6_6") (pintype "passive"))
      (node (ref "JP9") (pin "5") (pinfunction "5_5") (pintype "passive"))
      (node (ref "JP9") (pin "6") (pinfunction "6_6") (pintype "passive"))
      (node (ref "SV3") (pin "5") (pinfunction "S_5") (pintype "passive"))
    )
    (net (code "114") (name "Net-(SV3M-S)") (class "Default")
      (node (ref "JP13") (pin "5") (pinfunction "5_5") (pintype "passive"))
      (node (ref "JP13") (pin "6") (pinfunction "6_6") (pintype "passive"))
      (node (ref "JP14") (pin "5") (pinfunction "5_5") (pintype "passive"))
      (node (ref "JP14") (pin "6") (pinfunction "6_6") (pintype "passive"))
      (node (ref "SV3") (pin "6") (pinfunction "S_6") (pintype "passive"))
    )
    (net (code "115") (name "Net-(SV3O-S)") (class "Default")
      (node (ref "JP13") (pin "7") (pinfunction "7_7") (pintype "passive"))
      (node (ref "JP13") (pin "8") (pinfunction "8_8") (pintype "passive"))
      (node (ref "JP14") (pin "7") (pinfunction "7_7") (pintype "passive"))
      (node (ref "JP14") (pin "8") (pinfunction "8_8") (pintype "passive"))
      (node (ref "SV3") (pin "8") (pinfunction "S_8") (pintype "passive"))
    )
    (net (code "116") (name "Net-(SV3P-S)") (class "Default")
      (node (ref "JP12") (pin "10") (pinfunction "10_10") (pintype "passive"))
      (node (ref "JP12") (pin "9") (pinfunction "9_9") (pintype "passive"))
      (node (ref "JP9") (pin "10") (pinfunction "10_10") (pintype "passive"))
      (node (ref "JP9") (pin "9") (pinfunction "9_9") (pintype "passive"))
      (node (ref "SV3") (pin "9") (pinfunction "S_9") (pintype "passive"))
    )
    (net (code "117") (name "Net-(SV4A-S)") (class "Default")
      (node (ref "JP15") (pin "1") (pinfunction "1_1") (pintype "passive"))
      (node (ref "JP15") (pin "2") (pinfunction "2_2") (pintype "passive"))
      (node (ref "JP16") (pin "1") (pinfunction "1_1") (pintype "passive"))
      (node (ref "JP16") (pin "2") (pinfunction "2_2") (pintype "passive"))
      (node (ref "SV4") (pin "1") (pinfunction "S_1") (pintype "passive"))
    )
    (net (code "118") (name "Net-(SV4B-S)") (class "Default")
      (node (ref "JP17") (pin "10") (pinfunction "10_10") (pintype "passive"))
      (node (ref "JP17") (pin "9") (pinfunction "9_9") (pintype "passive"))
      (node (ref "JP18") (pin "10") (pinfunction "10_10") (pintype "passive"))
      (node (ref "JP18") (pin "9") (pinfunction "9_9") (pintype "passive"))
      (node (ref "SV4") (pin "10") (pinfunction "S_10") (pintype "passive"))
    )
    (net (code "119") (name "Net-(SV4C-S)") (class "Default")
      (node (ref "JP15") (pin "11") (pinfunction "11_11") (pintype "passive"))
      (node (ref "JP15") (pin "12") (pinfunction "12_12") (pintype "passive"))
      (node (ref "JP16") (pin "11") (pinfunction "11_11") (pintype "passive"))
      (node (ref "JP16") (pin "12") (pinfunction "12_12") (pintype "passive"))
      (node (ref "SV4") (pin "11") (pinfunction "S_11") (pintype "passive"))
    )
    (net (code "120") (name "Net-(SV4D-S)") (class "Default")
      (node (ref "JP17") (pin "11") (pinfunction "11_11") (pintype "passive"))
      (node (ref "JP17") (pin "12") (pinfunction "12_12") (pintype "passive"))
      (node (ref "JP18") (pin "11") (pinfunction "11_11") (pintype "passive"))
      (node (ref "JP18") (pin "12") (pinfunction "12_12") (pintype "passive"))
      (node (ref "SV4") (pin "12") (pinfunction "S_12") (pintype "passive"))
    )
    (net (code "121") (name "Net-(SV4E-S)") (class "Default")
      (node (ref "JP15") (pin "13") (pinfunction "13_13") (pintype "passive"))
      (node (ref "JP15") (pin "14") (pinfunction "14_14") (pintype "passive"))
      (node (ref "JP16") (pin "13") (pinfunction "13_13") (pintype "passive"))
      (node (ref "JP16") (pin "14") (pinfunction "14_14") (pintype "passive"))
      (node (ref "SV4") (pin "13") (pinfunction "S_13") (pintype "passive"))
    )
    (net (code "122") (name "Net-(SV4F-S)") (class "Default")
      (node (ref "JP17") (pin "13") (pinfunction "13_13") (pintype "passive"))
      (node (ref "JP17") (pin "14") (pinfunction "14_14") (pintype "passive"))
      (node (ref "JP18") (pin "13") (pinfunction "13_13") (pintype "passive"))
      (node (ref "JP18") (pin "14") (pinfunction "14_14") (pintype "passive"))
      (node (ref "SV4") (pin "14") (pinfunction "S_14") (pintype "passive"))
    )
    (net (code "123") (name "Net-(SV4G-S)") (class "Default")
      (node (ref "JP15") (pin "15") (pinfunction "15_15") (pintype "passive"))
      (node (ref "JP15") (pin "16") (pinfunction "16_16") (pintype "passive"))
      (node (ref "JP16") (pin "15") (pinfunction "15_15") (pintype "passive"))
      (node (ref "JP16") (pin "16") (pinfunction "16_16") (pintype "passive"))
      (node (ref "SV4") (pin "15") (pinfunction "S_15") (pintype "passive"))
    )
    (net (code "124") (name "Net-(SV4H-S)") (class "Default")
      (node (ref "JP17") (pin "15") (pinfunction "15_15") (pintype "passive"))
      (node (ref "JP17") (pin "16") (pinfunction "16_16") (pintype "passive"))
      (node (ref "JP18") (pin "15") (pinfunction "15_15") (pintype "passive"))
      (node (ref "JP18") (pin "16") (pinfunction "16_16") (pintype "passive"))
      (node (ref "SV4") (pin "16") (pinfunction "S_16") (pintype "passive"))
    )
    (net (code "125") (name "Net-(SV4I-S)") (class "Default")
      (node (ref "JP17") (pin "1") (pinfunction "1_1") (pintype "passive"))
      (node (ref "JP17") (pin "2") (pinfunction "2_2") (pintype "passive"))
      (node (ref "JP18") (pin "1") (pinfunction "1_1") (pintype "passive"))
      (node (ref "JP18") (pin "2") (pinfunction "2_2") (pintype "passive"))
      (node (ref "SV4") (pin "2") (pinfunction "S_2") (pintype "passive"))
    )
    (net (code "126") (name "Net-(SV4J-S)") (class "Default")
      (node (ref "JP15") (pin "3") (pinfunction "3_3") (pintype "passive"))
      (node (ref "JP15") (pin "4") (pinfunction "4_4") (pintype "passive"))
      (node (ref "JP16") (pin "3") (pinfunction "3_3") (pintype "passive"))
      (node (ref "JP16") (pin "4") (pinfunction "4_4") (pintype "passive"))
      (node (ref "SV4") (pin "3") (pinfunction "S_3") (pintype "passive"))
    )
    (net (code "127") (name "Net-(SV4K-S)") (class "Default")
      (node (ref "JP17") (pin "3") (pinfunction "3_3") (pintype "passive"))
      (node (ref "JP17") (pin "4") (pinfunction "4_4") (pintype "passive"))
      (node (ref "JP18") (pin "3") (pinfunction "3_3") (pintype "passive"))
      (node (ref "JP18") (pin "4") (pinfunction "4_4") (pintype "passive"))
      (node (ref "SV4") (pin "4") (pinfunction "S_4") (pintype "passive"))
    )
    (net (code "128") (name "Net-(SV4L-S)") (class "Default")
      (node (ref "JP15") (pin "5") (pinfunction "5_5") (pintype "passive"))
      (node (ref "JP15") (pin "6") (pinfunction "6_6") (pintype "passive"))
      (node (ref "JP16") (pin "5") (pinfunction "5_5") (pintype "passive"))
      (node (ref "JP16") (pin "6") (pinfunction "6_6") (pintype "passive"))
      (node (ref "SV4") (pin "5") (pinfunction "S_5") (pintype "passive"))
    )
    (net (code "129") (name "Net-(SV4M-S)") (class "Default")
      (node (ref "JP17") (pin "5") (pinfunction "5_5") (pintype "passive"))
      (node (ref "JP17") (pin "6") (pinfunction "6_6") (pintype "passive"))
      (node (ref "JP18") (pin "5") (pinfunction "5_5") (pintype "passive"))
      (node (ref "JP18") (pin "6") (pinfunction "6_6") (pintype "passive"))
      (node (ref "SV4") (pin "6") (pinfunction "S_6") (pintype "passive"))
    )
    (net (code "130") (name "Net-(SV4N-S)") (class "Default")
      (node (ref "JP15") (pin "7") (pinfunction "7_7") (pintype "passive"))
      (node (ref "JP15") (pin "8") (pinfunction "8_8") (pintype "passive"))
      (node (ref "JP16") (pin "7") (pinfunction "7_7") (pintype "passive"))
      (node (ref "JP16") (pin "8") (pinfunction "8_8") (pintype "passive"))
      (node (ref "SV4") (pin "7") (pinfunction "S_7") (pintype "passive"))
    )
    (net (code "131") (name "Net-(SV4O-S)") (class "Default")
      (node (ref "JP17") (pin "7") (pinfunction "7_7") (pintype "passive"))
      (node (ref "JP17") (pin "8") (pinfunction "8_8") (pintype "passive"))
      (node (ref "JP18") (pin "7") (pinfunction "7_7") (pintype "passive"))
      (node (ref "JP18") (pin "8") (pinfunction "8_8") (pintype "passive"))
      (node (ref "SV4") (pin "8") (pinfunction "S_8") (pintype "passive"))
    )
    (net (code "132") (name "Net-(SV4P-S)") (class "Default")
      (node (ref "JP15") (pin "10") (pinfunction "10_10") (pintype "passive"))
      (node (ref "JP15") (pin "9") (pinfunction "9_9") (pintype "passive"))
      (node (ref "JP16") (pin "10") (pinfunction "10_10") (pintype "passive"))
      (node (ref "JP16") (pin "9") (pinfunction "9_9") (pintype "passive"))
      (node (ref "SV4") (pin "9") (pinfunction "S_9") (pintype "passive"))
    )
    (net (code "133") (name "Net-(SV5A-S)") (class "Default")
      (node (ref "JP19") (pin "1") (pinfunction "1_1") (pintype "passive"))
      (node (ref "JP19") (pin "2") (pinfunction "2_2") (pintype "passive"))
      (node (ref "JP20") (pin "1") (pinfunction "1_1") (pintype "passive"))
      (node (ref "JP20") (pin "2") (pinfunction "2_2") (pintype "passive"))
      (node (ref "SV5") (pin "1") (pinfunction "S_1") (pintype "passive"))
    )
    (net (code "134") (name "Net-(SV5B-S)") (class "Default")
      (node (ref "JP21") (pin "10") (pinfunction "10_10") (pintype "passive"))
      (node (ref "JP21") (pin "9") (pinfunction "9_9") (pintype "passive"))
      (node (ref "JP22") (pin "10") (pinfunction "10_10") (pintype "passive"))
      (node (ref "JP22") (pin "9") (pinfunction "9_9") (pintype "passive"))
      (node (ref "SV5") (pin "10") (pinfunction "S_10") (pintype "passive"))
    )
    (net (code "135") (name "Net-(SV5C-S)") (class "Default")
      (node (ref "JP19") (pin "11") (pinfunction "11_11") (pintype "passive"))
      (node (ref "JP19") (pin "12") (pinfunction "12_12") (pintype "passive"))
      (node (ref "JP20") (pin "11") (pinfunction "11_11") (pintype "passive"))
      (node (ref "JP20") (pin "12") (pinfunction "12_12") (pintype "passive"))
      (node (ref "SV5") (pin "11") (pinfunction "S_11") (pintype "passive"))
    )
    (net (code "136") (name "Net-(SV5D-S)") (class "Default")
      (node (ref "JP21") (pin "11") (pinfunction "11_11") (pintype "passive"))
      (node (ref "JP21") (pin "12") (pinfunction "12_12") (pintype "passive"))
      (node (ref "JP22") (pin "11") (pinfunction "11_11") (pintype "passive"))
      (node (ref "JP22") (pin "12") (pinfunction "12_12") (pintype "passive"))
      (node (ref "SV5") (pin "12") (pinfunction "S_12") (pintype "passive"))
    )
    (net (code "137") (name "Net-(SV5E-S)") (class "Default")
      (node (ref "JP19") (pin "13") (pinfunction "13_13") (pintype "passive"))
      (node (ref "JP19") (pin "14") (pinfunction "14_14") (pintype "passive"))
      (node (ref "JP20") (pin "13") (pinfunction "13_13") (pintype "passive"))
      (node (ref "JP20") (pin "14") (pinfunction "14_14") (pintype "passive"))
      (node (ref "SV5") (pin "13") (pinfunction "S_13") (pintype "passive"))
    )
    (net (code "138") (name "Net-(SV5F-S)") (class "Default")
      (node (ref "JP21") (pin "13") (pinfunction "13_13") (pintype "passive"))
      (node (ref "JP21") (pin "14") (pinfunction "14_14") (pintype "passive"))
      (node (ref "JP22") (pin "13") (pinfunction "13_13") (pintype "passive"))
      (node (ref "JP22") (pin "14") (pinfunction "14_14") (pintype "passive"))
      (node (ref "SV5") (pin "14") (pinfunction "S_14") (pintype "passive"))
    )
    (net (code "139") (name "Net-(SV5G-S)") (class "Default")
      (node (ref "JP19") (pin "15") (pinfunction "15_15") (pintype "passive"))
      (node (ref "JP19") (pin "16") (pinfunction "16_16") (pintype "passive"))
      (node (ref "JP20") (pin "15") (pinfunction "15_15") (pintype "passive"))
      (node (ref "JP20") (pin "16") (pinfunction "16_16") (pintype "passive"))
      (node (ref "SV5") (pin "15") (pinfunction "S_15") (pintype "passive"))
    )
    (net (code "140") (name "Net-(SV5H-S)") (class "Default")
      (node (ref "JP21") (pin "15") (pinfunction "15_15") (pintype "passive"))
      (node (ref "JP21") (pin "16") (pinfunction "16_16") (pintype "passive"))
      (node (ref "JP22") (pin "15") (pinfunction "15_15") (pintype "passive"))
      (node (ref "JP22") (pin "16") (pinfunction "16_16") (pintype "passive"))
      (node (ref "SV5") (pin "16") (pinfunction "S_16") (pintype "passive"))
    )
    (net (code "141") (name "Net-(SV5I-S)") (class "Default")
      (node (ref "JP21") (pin "1") (pinfunction "1_1") (pintype "passive"))
      (node (ref "JP21") (pin "2") (pinfunction "2_2") (pintype "passive"))
      (node (ref "JP22") (pin "1") (pinfunction "1_1") (pintype "passive"))
      (node (ref "JP22") (pin "2") (pinfunction "2_2") (pintype "passive"))
      (node (ref "SV5") (pin "2") (pinfunction "S_2") (pintype "passive"))
    )
    (net (code "142") (name "Net-(SV5J-S)") (class "Default")
      (node (ref "JP19") (pin "3") (pinfunction "3_3") (pintype "passive"))
      (node (ref "JP19") (pin "4") (pinfunction "4_4") (pintype "passive"))
      (node (ref "JP20") (pin "3") (pinfunction "3_3") (pintype "passive"))
      (node (ref "JP20") (pin "4") (pinfunction "4_4") (pintype "passive"))
      (node (ref "SV5") (pin "3") (pinfunction "S_3") (pintype "passive"))
    )
    (net (code "143") (name "Net-(SV5K-S)") (class "Default")
      (node (ref "JP21") (pin "3") (pinfunction "3_3") (pintype "passive"))
      (node (ref "JP21") (pin "4") (pinfunction "4_4") (pintype "passive"))
      (node (ref "JP22") (pin "3") (pinfunction "3_3") (pintype "passive"))
      (node (ref "JP22") (pin "4") (pinfunction "4_4") (pintype "passive"))
      (node (ref "SV5") (pin "4") (pinfunction "S_4") (pintype "passive"))
    )
    (net (code "144") (name "Net-(SV5L-S)") (class "Default")
      (node (ref "JP19") (pin "5") (pinfunction "5_5") (pintype "passive"))
      (node (ref "JP19") (pin "6") (pinfunction "6_6") (pintype "passive"))
      (node (ref "JP20") (pin "5") (pinfunction "5_5") (pintype "passive"))
      (node (ref "JP20") (pin "6") (pinfunction "6_6") (pintype "passive"))
      (node (ref "SV5") (pin "5") (pinfunction "S_5") (pintype "passive"))
    )
    (net (code "145") (name "Net-(SV5M-S)") (class "Default")
      (node (ref "JP21") (pin "5") (pinfunction "5_5") (pintype "passive"))
      (node (ref "JP21") (pin "6") (pinfunction "6_6") (pintype "passive"))
      (node (ref "JP22") (pin "5") (pinfunction "5_5") (pintype "passive"))
      (node (ref "JP22") (pin "6") (pinfunction "6_6") (pintype "passive"))
      (node (ref "SV5") (pin "6") (pinfunction "S_6") (pintype "passive"))
    )
    (net (code "146") (name "Net-(SV5N-S)") (class "Default")
      (node (ref "JP19") (pin "7") (pinfunction "7_7") (pintype "passive"))
      (node (ref "JP19") (pin "8") (pinfunction "8_8") (pintype "passive"))
      (node (ref "JP20") (pin "7") (pinfunction "7_7") (pintype "passive"))
      (node (ref "JP20") (pin "8") (pinfunction "8_8") (pintype "passive"))
      (node (ref "SV5") (pin "7") (pinfunction "S_7") (pintype "passive"))
    )
    (net (code "147") (name "Net-(SV5O-S)") (class "Default")
      (node (ref "JP21") (pin "7") (pinfunction "7_7") (pintype "passive"))
      (node (ref "JP21") (pin "8") (pinfunction "8_8") (pintype "passive"))
      (node (ref "JP22") (pin "7") (pinfunction "7_7") (pintype "passive"))
      (node (ref "JP22") (pin "8") (pinfunction "8_8") (pintype "passive"))
      (node (ref "SV5") (pin "8") (pinfunction "S_8") (pintype "passive"))
    )
    (net (code "148") (name "Net-(SV5P-S)") (class "Default")
      (node (ref "JP19") (pin "10") (pinfunction "10_10") (pintype "passive"))
      (node (ref "JP19") (pin "9") (pinfunction "9_9") (pintype "passive"))
      (node (ref "JP20") (pin "10") (pinfunction "10_10") (pintype "passive"))
      (node (ref "JP20") (pin "9") (pinfunction "9_9") (pintype "passive"))
      (node (ref "SV5") (pin "9") (pinfunction "S_9") (pintype "passive"))
    )
    (net (code "149") (name "Net-(SV6A-S)") (class "Default")
      (node (ref "JP23") (pin "1") (pinfunction "1_1") (pintype "passive"))
      (node (ref "JP23") (pin "2") (pinfunction "2_2") (pintype "passive"))
      (node (ref "JP24") (pin "1") (pinfunction "1_1") (pintype "passive"))
      (node (ref "JP24") (pin "2") (pinfunction "2_2") (pintype "passive"))
      (node (ref "SV6") (pin "1") (pinfunction "S_1") (pintype "passive"))
    )
    (net (code "150") (name "Net-(SV6B-S)") (class "Default")
      (node (ref "JP25") (pin "10") (pinfunction "10_10") (pintype "passive"))
      (node (ref "JP25") (pin "9") (pinfunction "9_9") (pintype "passive"))
      (node (ref "JP26") (pin "10") (pinfunction "10_10") (pintype "passive"))
      (node (ref "JP26") (pin "9") (pinfunction "9_9") (pintype "passive"))
      (node (ref "SV6") (pin "10") (pinfunction "S_10") (pintype "passive"))
    )
    (net (code "151") (name "Net-(SV6C-S)") (class "Default")
      (node (ref "JP23") (pin "11") (pinfunction "11_11") (pintype "passive"))
      (node (ref "JP23") (pin "12") (pinfunction "12_12") (pintype "passive"))
      (node (ref "JP24") (pin "11") (pinfunction "11_11") (pintype "passive"))
      (node (ref "JP24") (pin "12") (pinfunction "12_12") (pintype "passive"))
      (node (ref "SV6") (pin "11") (pinfunction "S_11") (pintype "passive"))
    )
    (net (code "152") (name "Net-(SV6D-S)") (class "Default")
      (node (ref "JP25") (pin "11") (pinfunction "11_11") (pintype "passive"))
      (node (ref "JP25") (pin "12") (pinfunction "12_12") (pintype "passive"))
      (node (ref "JP26") (pin "11") (pinfunction "11_11") (pintype "passive"))
      (node (ref "JP26") (pin "12") (pinfunction "12_12") (pintype "passive"))
      (node (ref "SV6") (pin "12") (pinfunction "S_12") (pintype "passive"))
    )
    (net (code "153") (name "Net-(SV6E-S)") (class "Default")
      (node (ref "JP23") (pin "13") (pinfunction "13_13") (pintype "passive"))
      (node (ref "JP23") (pin "14") (pinfunction "14_14") (pintype "passive"))
      (node (ref "JP24") (pin "13") (pinfunction "13_13") (pintype "passive"))
      (node (ref "JP24") (pin "14") (pinfunction "14_14") (pintype "passive"))
      (node (ref "SV6") (pin "13") (pinfunction "S_13") (pintype "passive"))
    )
    (net (code "154") (name "Net-(SV6F-S)") (class "Default")
      (node (ref "JP25") (pin "13") (pinfunction "13_13") (pintype "passive"))
      (node (ref "JP25") (pin "14") (pinfunction "14_14") (pintype "passive"))
      (node (ref "JP26") (pin "13") (pinfunction "13_13") (pintype "passive"))
      (node (ref "JP26") (pin "14") (pinfunction "14_14") (pintype "passive"))
      (node (ref "SV6") (pin "14") (pinfunction "S_14") (pintype "passive"))
    )
    (net (code "155") (name "Net-(SV6G-S)") (class "Default")
      (node (ref "JP23") (pin "15") (pinfunction "15_15") (pintype "passive"))
      (node (ref "JP23") (pin "16") (pinfunction "16_16") (pintype "passive"))
      (node (ref "JP24") (pin "15") (pinfunction "15_15") (pintype "passive"))
      (node (ref "JP24") (pin "16") (pinfunction "16_16") (pintype "passive"))
      (node (ref "SV6") (pin "15") (pinfunction "S_15") (pintype "passive"))
    )
    (net (code "156") (name "Net-(SV6H-S)") (class "Default")
      (node (ref "JP25") (pin "15") (pinfunction "15_15") (pintype "passive"))
      (node (ref "JP25") (pin "16") (pinfunction "16_16") (pintype "passive"))
      (node (ref "JP26") (pin "15") (pinfunction "15_15") (pintype "passive"))
      (node (ref "JP26") (pin "16") (pinfunction "16_16") (pintype "passive"))
      (node (ref "SV6") (pin "16") (pinfunction "S_16") (pintype "passive"))
    )
    (net (code "157") (name "Net-(SV6I-S)") (class "Default")
      (node (ref "JP25") (pin "1") (pinfunction "1_1") (pintype "passive"))
      (node (ref "JP25") (pin "2") (pinfunction "2_2") (pintype "passive"))
      (node (ref "JP26") (pin "1") (pinfunction "1_1") (pintype "passive"))
      (node (ref "JP26") (pin "2") (pinfunction "2_2") (pintype "passive"))
      (node (ref "SV6") (pin "2") (pinfunction "S_2") (pintype "passive"))
    )
    (net (code "158") (name "Net-(SV6J-S)") (class "Default")
      (node (ref "JP23") (pin "3") (pinfunction "3_3") (pintype "passive"))
      (node (ref "JP23") (pin "4") (pinfunction "4_4") (pintype "passive"))
      (node (ref "JP24") (pin "3") (pinfunction "3_3") (pintype "passive"))
      (node (ref "JP24") (pin "4") (pinfunction "4_4") (pintype "passive"))
      (node (ref "SV6") (pin "3") (pinfunction "S_3") (pintype "passive"))
    )
    (net (code "159") (name "Net-(SV6K-S)") (class "Default")
      (node (ref "JP25") (pin "3") (pinfunction "3_3") (pintype "passive"))
      (node (ref "JP25") (pin "4") (pinfunction "4_4") (pintype "passive"))
      (node (ref "JP26") (pin "3") (pinfunction "3_3") (pintype "passive"))
      (node (ref "JP26") (pin "4") (pinfunction "4_4") (pintype "passive"))
      (node (ref "SV6") (pin "4") (pinfunction "S_4") (pintype "passive"))
    )
    (net (code "160") (name "Net-(SV6L-S)") (class "Default")
      (node (ref "JP23") (pin "5") (pinfunction "5_5") (pintype "passive"))
      (node (ref "JP23") (pin "6") (pinfunction "6_6") (pintype "passive"))
      (node (ref "JP24") (pin "5") (pinfunction "5_5") (pintype "passive"))
      (node (ref "JP24") (pin "6") (pinfunction "6_6") (pintype "passive"))
      (node (ref "SV6") (pin "5") (pinfunction "S_5") (pintype "passive"))
    )
    (net (code "161") (name "Net-(SV6M-S)") (class "Default")
      (node (ref "JP25") (pin "5") (pinfunction "5_5") (pintype "passive"))
      (node (ref "JP25") (pin "6") (pinfunction "6_6") (pintype "passive"))
      (node (ref "JP26") (pin "5") (pinfunction "5_5") (pintype "passive"))
      (node (ref "JP26") (pin "6") (pinfunction "6_6") (pintype "passive"))
      (node (ref "SV6") (pin "6") (pinfunction "S_6") (pintype "passive"))
    )
    (net (code "162") (name "Net-(SV6N-S)") (class "Default")
      (node (ref "JP23") (pin "7") (pinfunction "7_7") (pintype "passive"))
      (node (ref "JP23") (pin "8") (pinfunction "8_8") (pintype "passive"))
      (node (ref "JP24") (pin "7") (pinfunction "7_7") (pintype "passive"))
      (node (ref "JP24") (pin "8") (pinfunction "8_8") (pintype "passive"))
      (node (ref "SV6") (pin "7") (pinfunction "S_7") (pintype "passive"))
    )
    (net (code "163") (name "Net-(SV6O-S)") (class "Default")
      (node (ref "JP25") (pin "7") (pinfunction "7_7") (pintype "passive"))
      (node (ref "JP25") (pin "8") (pinfunction "8_8") (pintype "passive"))
      (node (ref "JP26") (pin "7") (pinfunction "7_7") (pintype "passive"))
      (node (ref "JP26") (pin "8") (pinfunction "8_8") (pintype "passive"))
      (node (ref "SV6") (pin "8") (pinfunction "S_8") (pintype "passive"))
    )
    (net (code "164") (name "Net-(SV6P-S)") (class "Default")
      (node (ref "JP23") (pin "10") (pinfunction "10_10") (pintype "passive"))
      (node (ref "JP23") (pin "9") (pinfunction "9_9") (pintype "passive"))
      (node (ref "JP24") (pin "10") (pinfunction "10_10") (pintype "passive"))
      (node (ref "JP24") (pin "9") (pinfunction "9_9") (pintype "passive"))
      (node (ref "SV6") (pin "9") (pinfunction "S_9") (pintype "passive"))
    )
  )
)
